# NT1X68BC.net
KiCad netlist of a schematic drawn in EAGLE
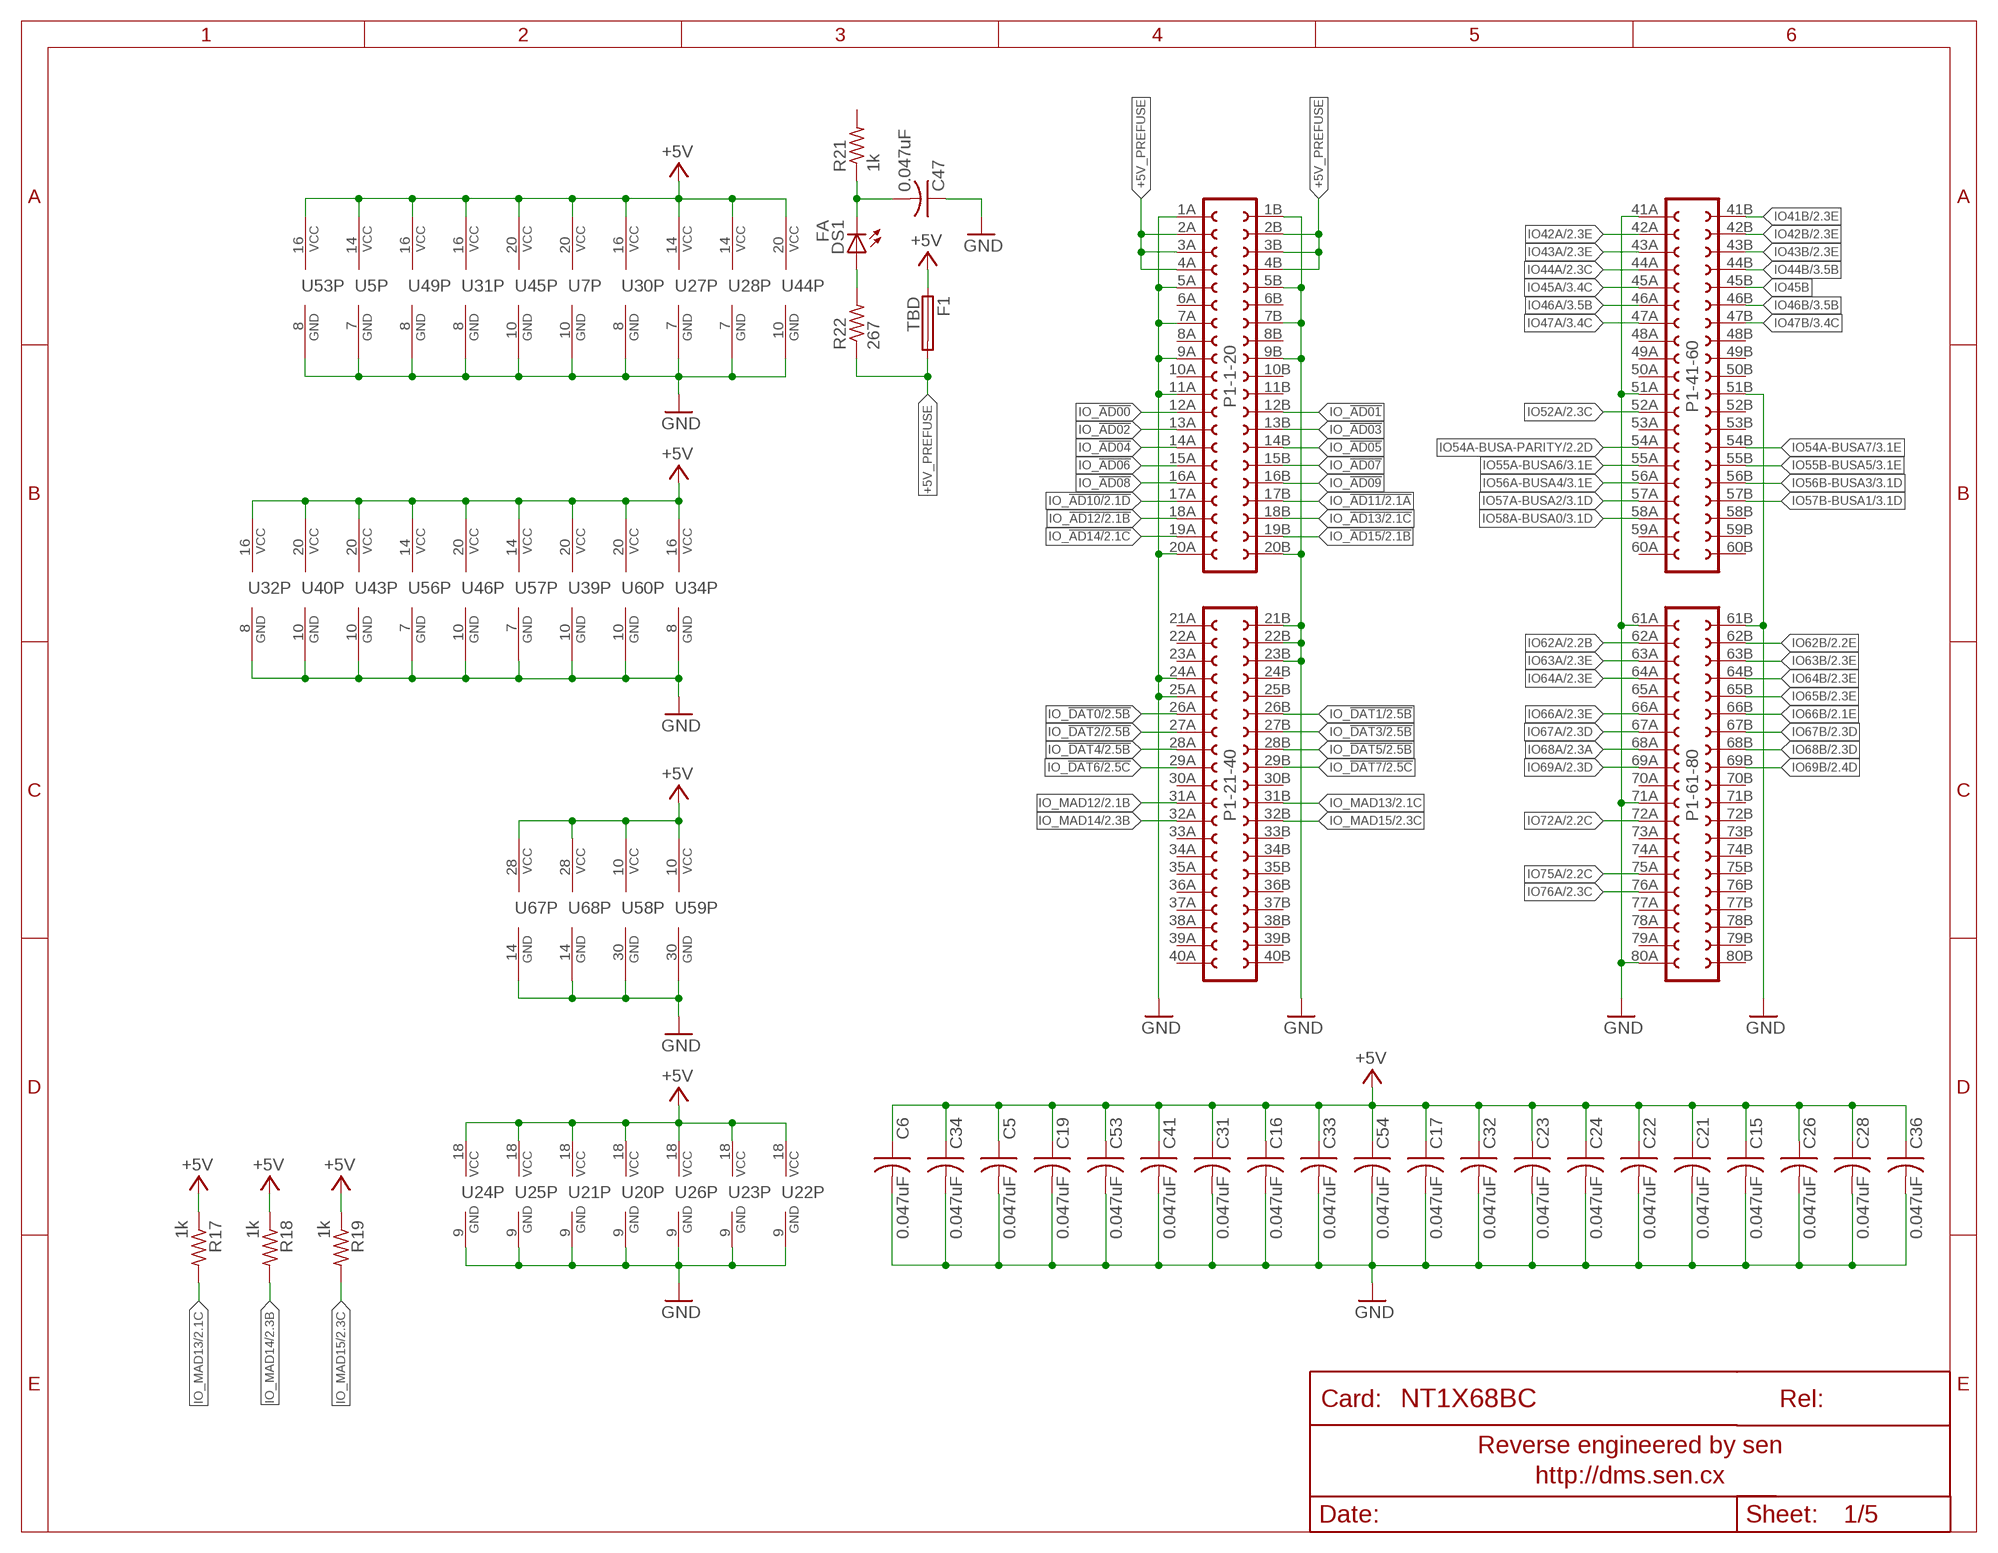
[diagram p0: schematic, sheet 1]
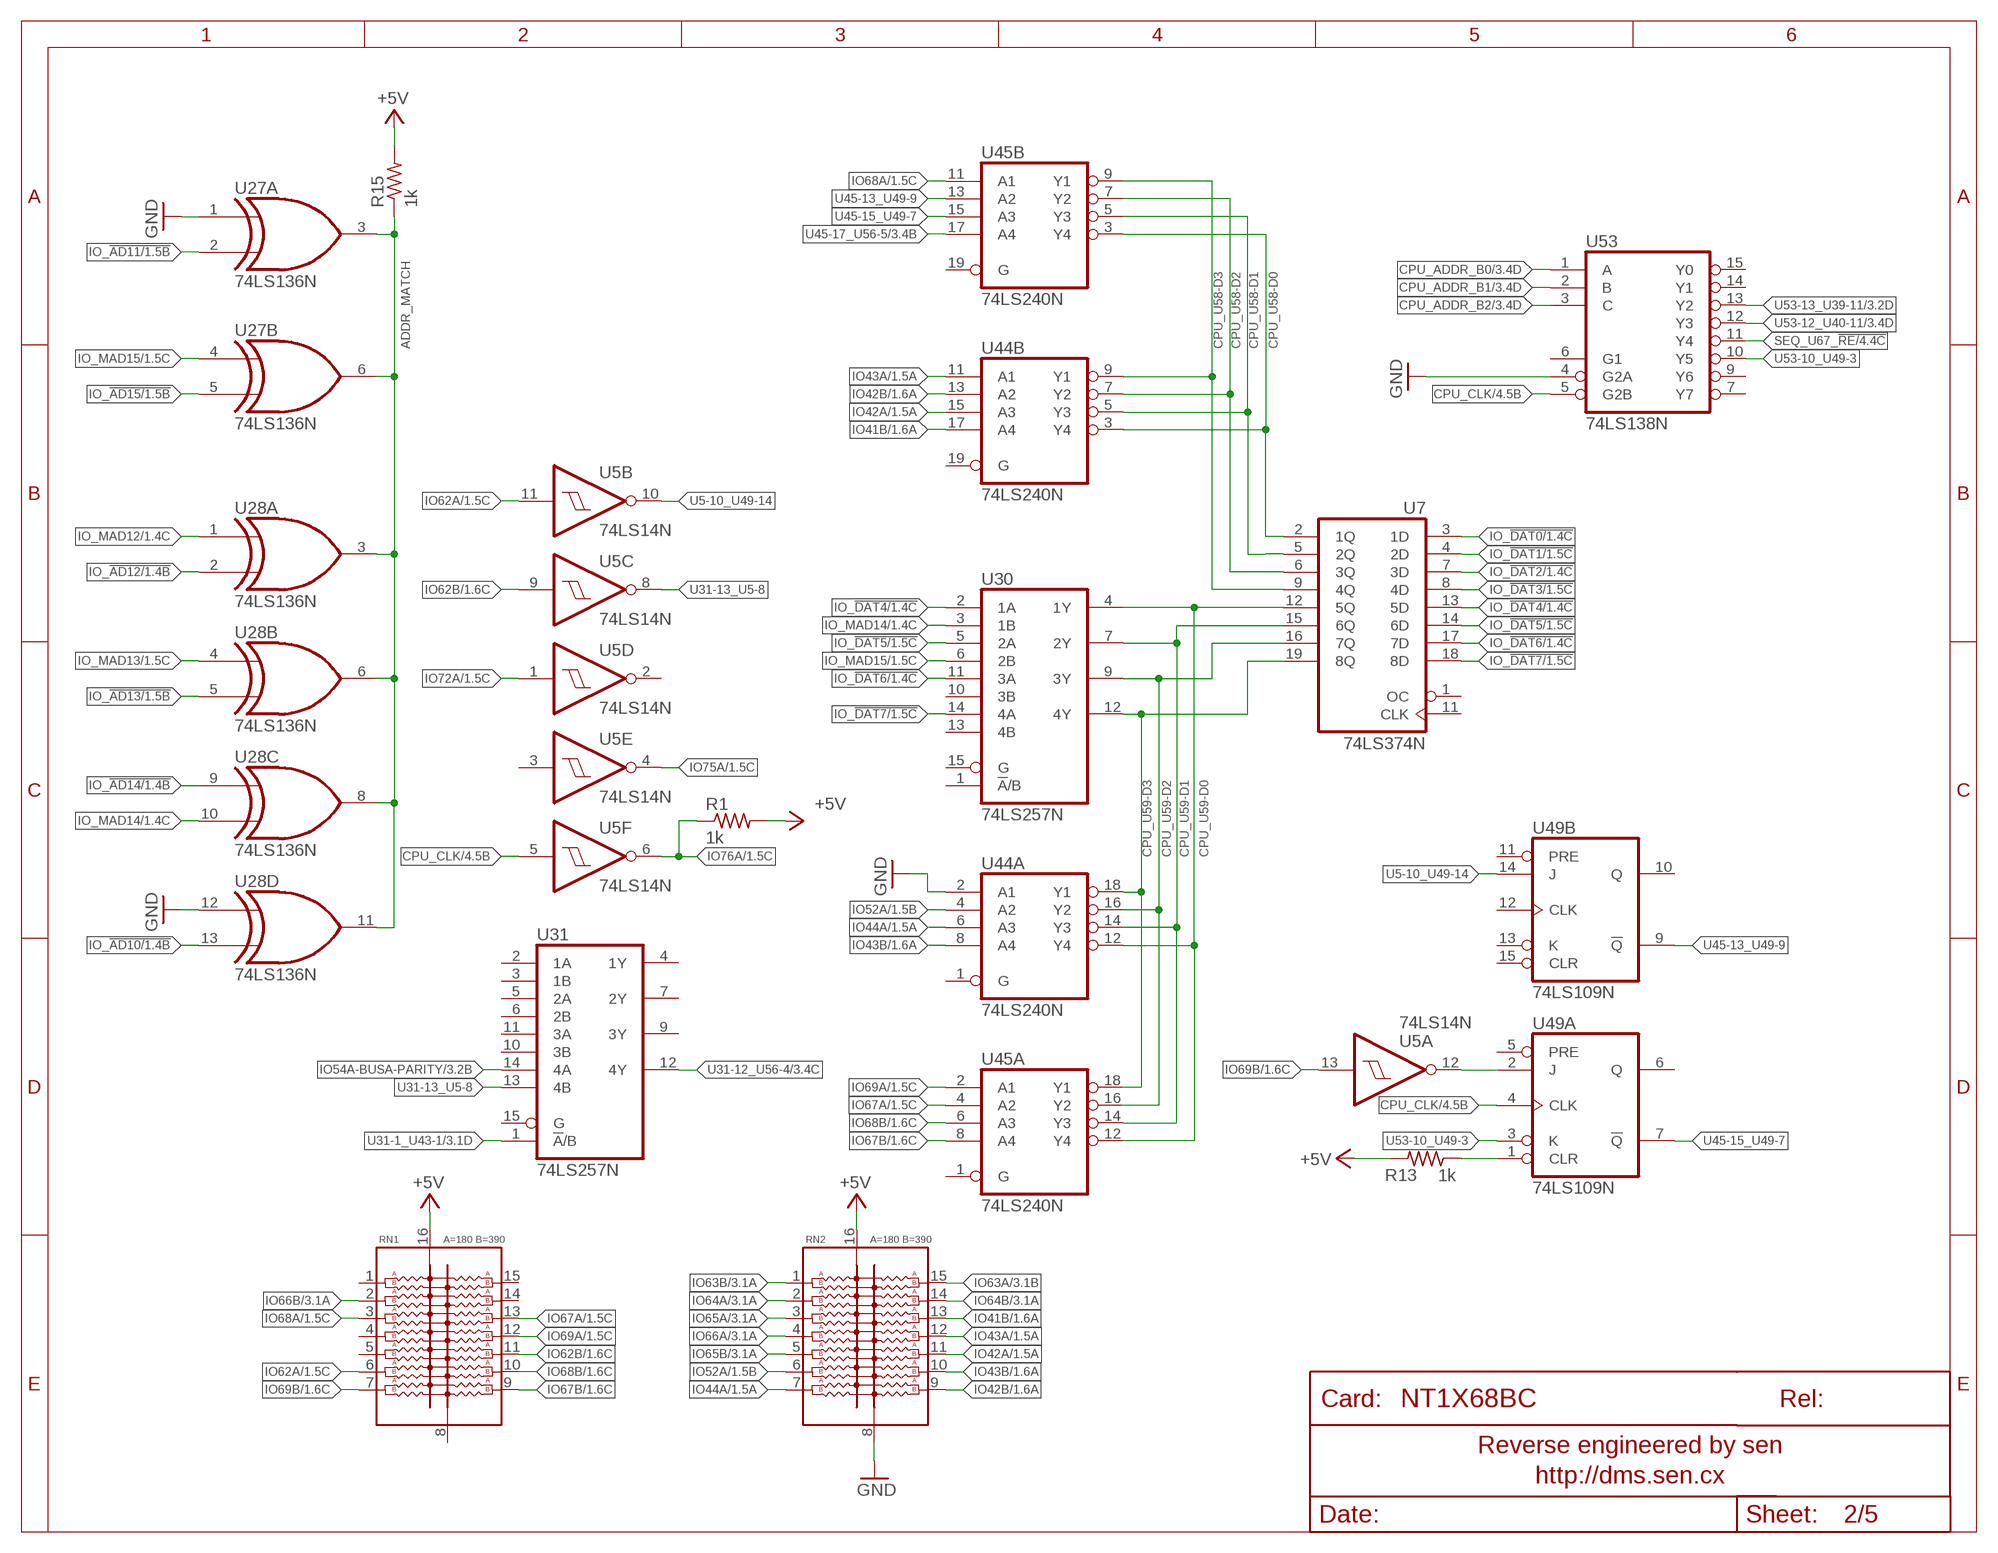
[diagram p1: schematic, sheet 2]
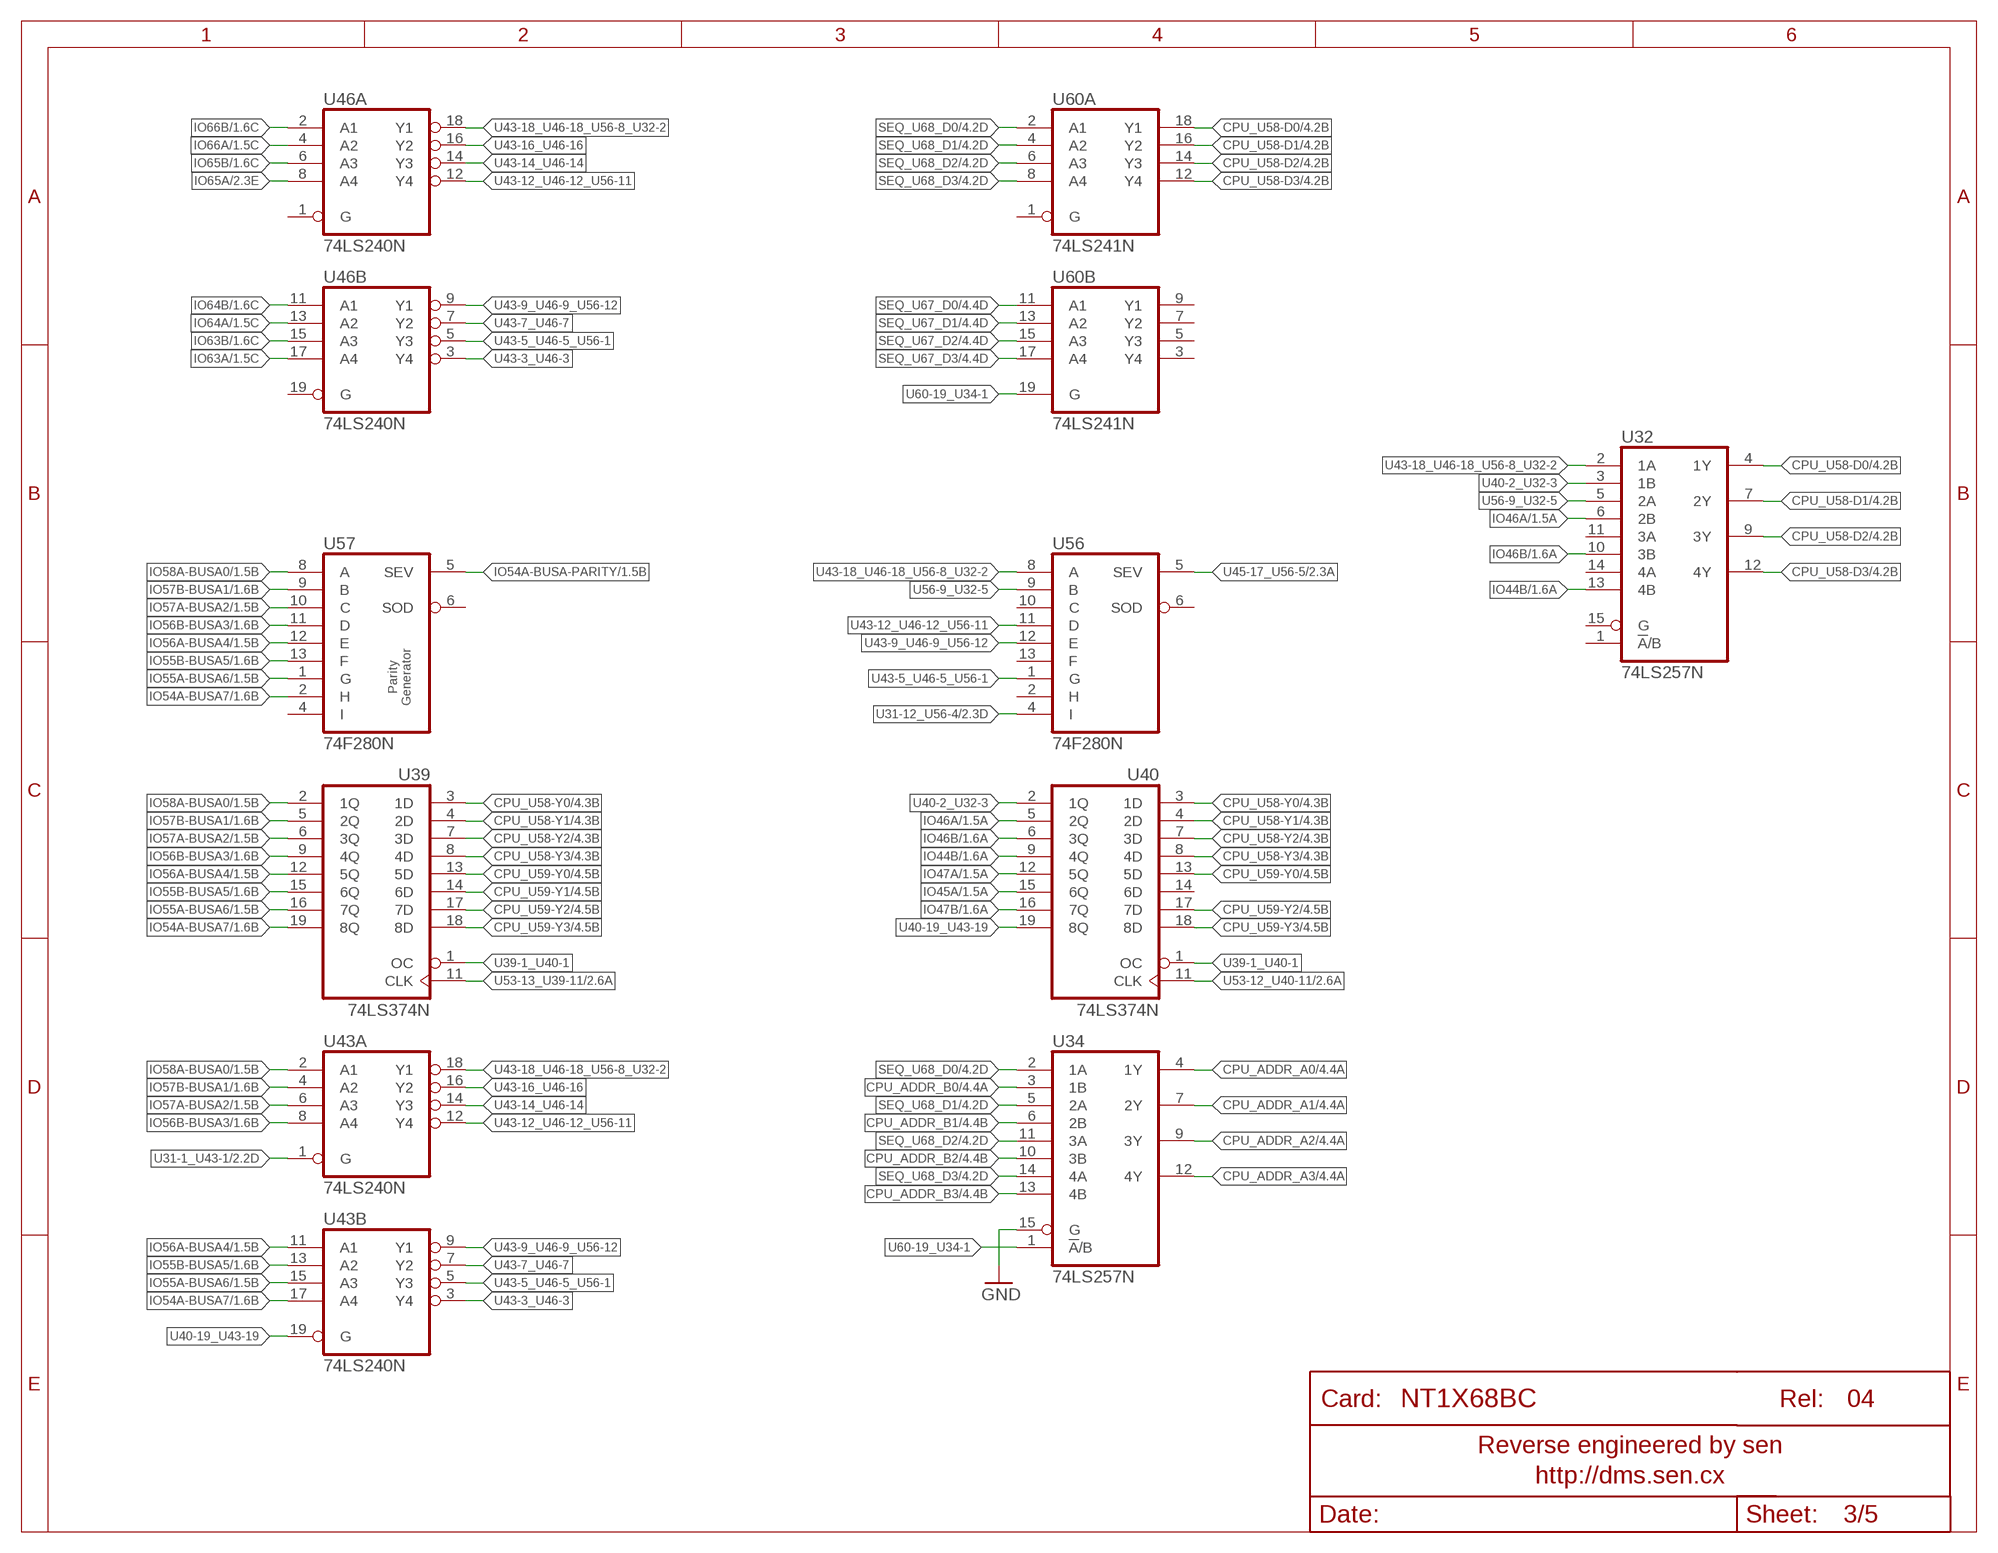
[diagram p2: schematic, sheet 3]
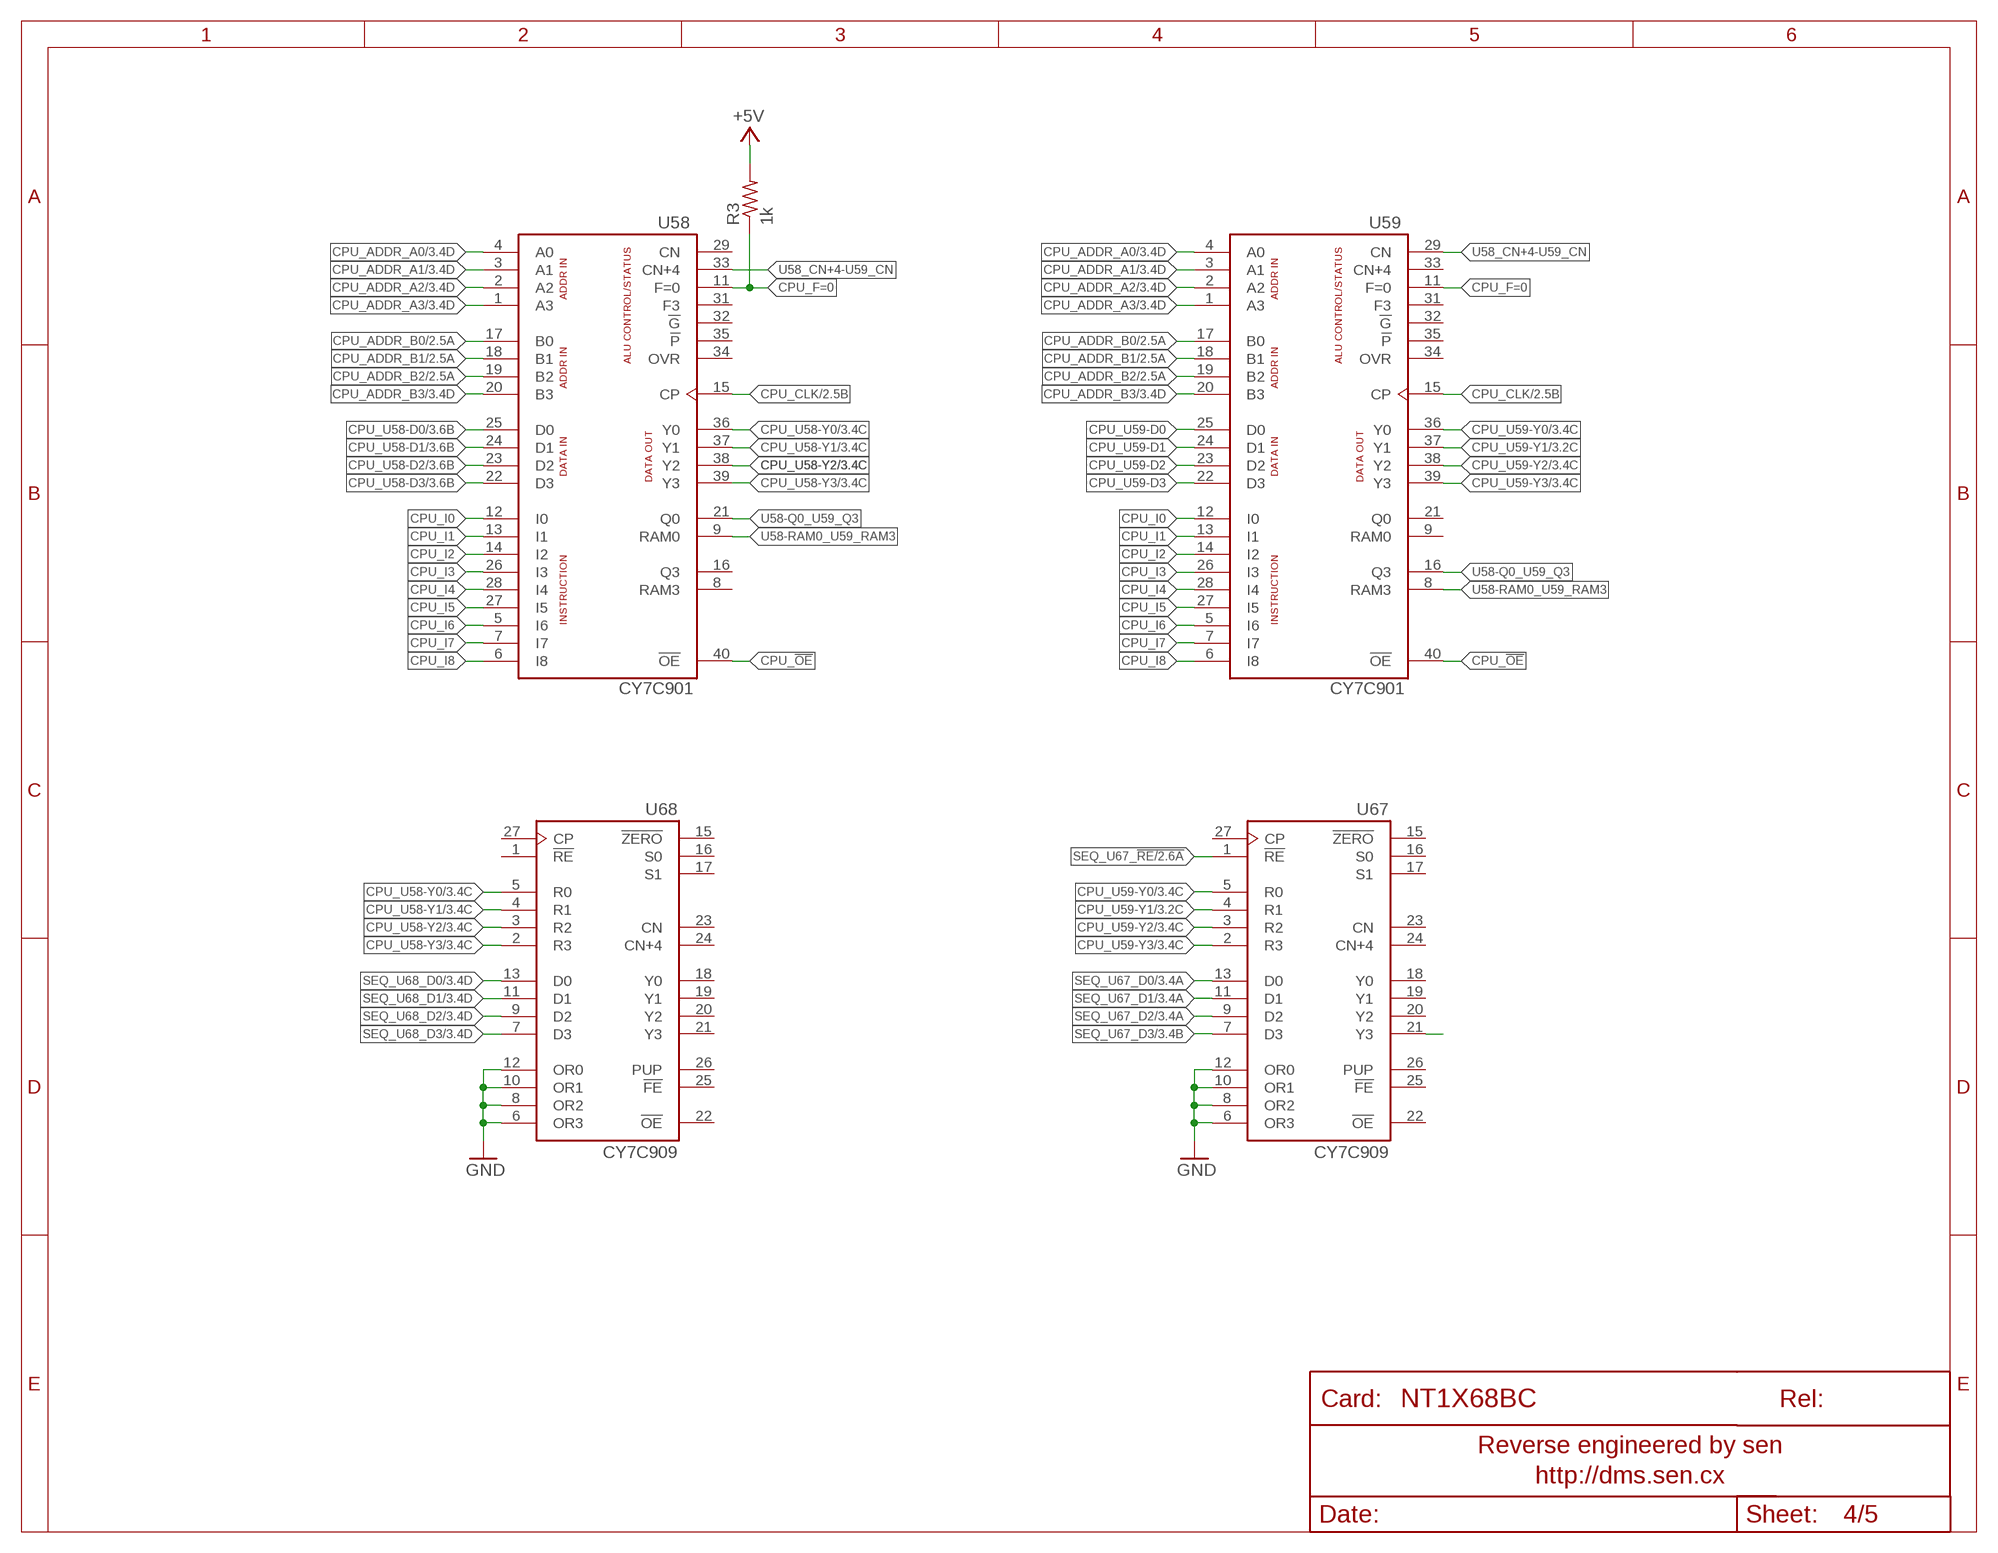
[diagram p3: schematic, sheet 4]
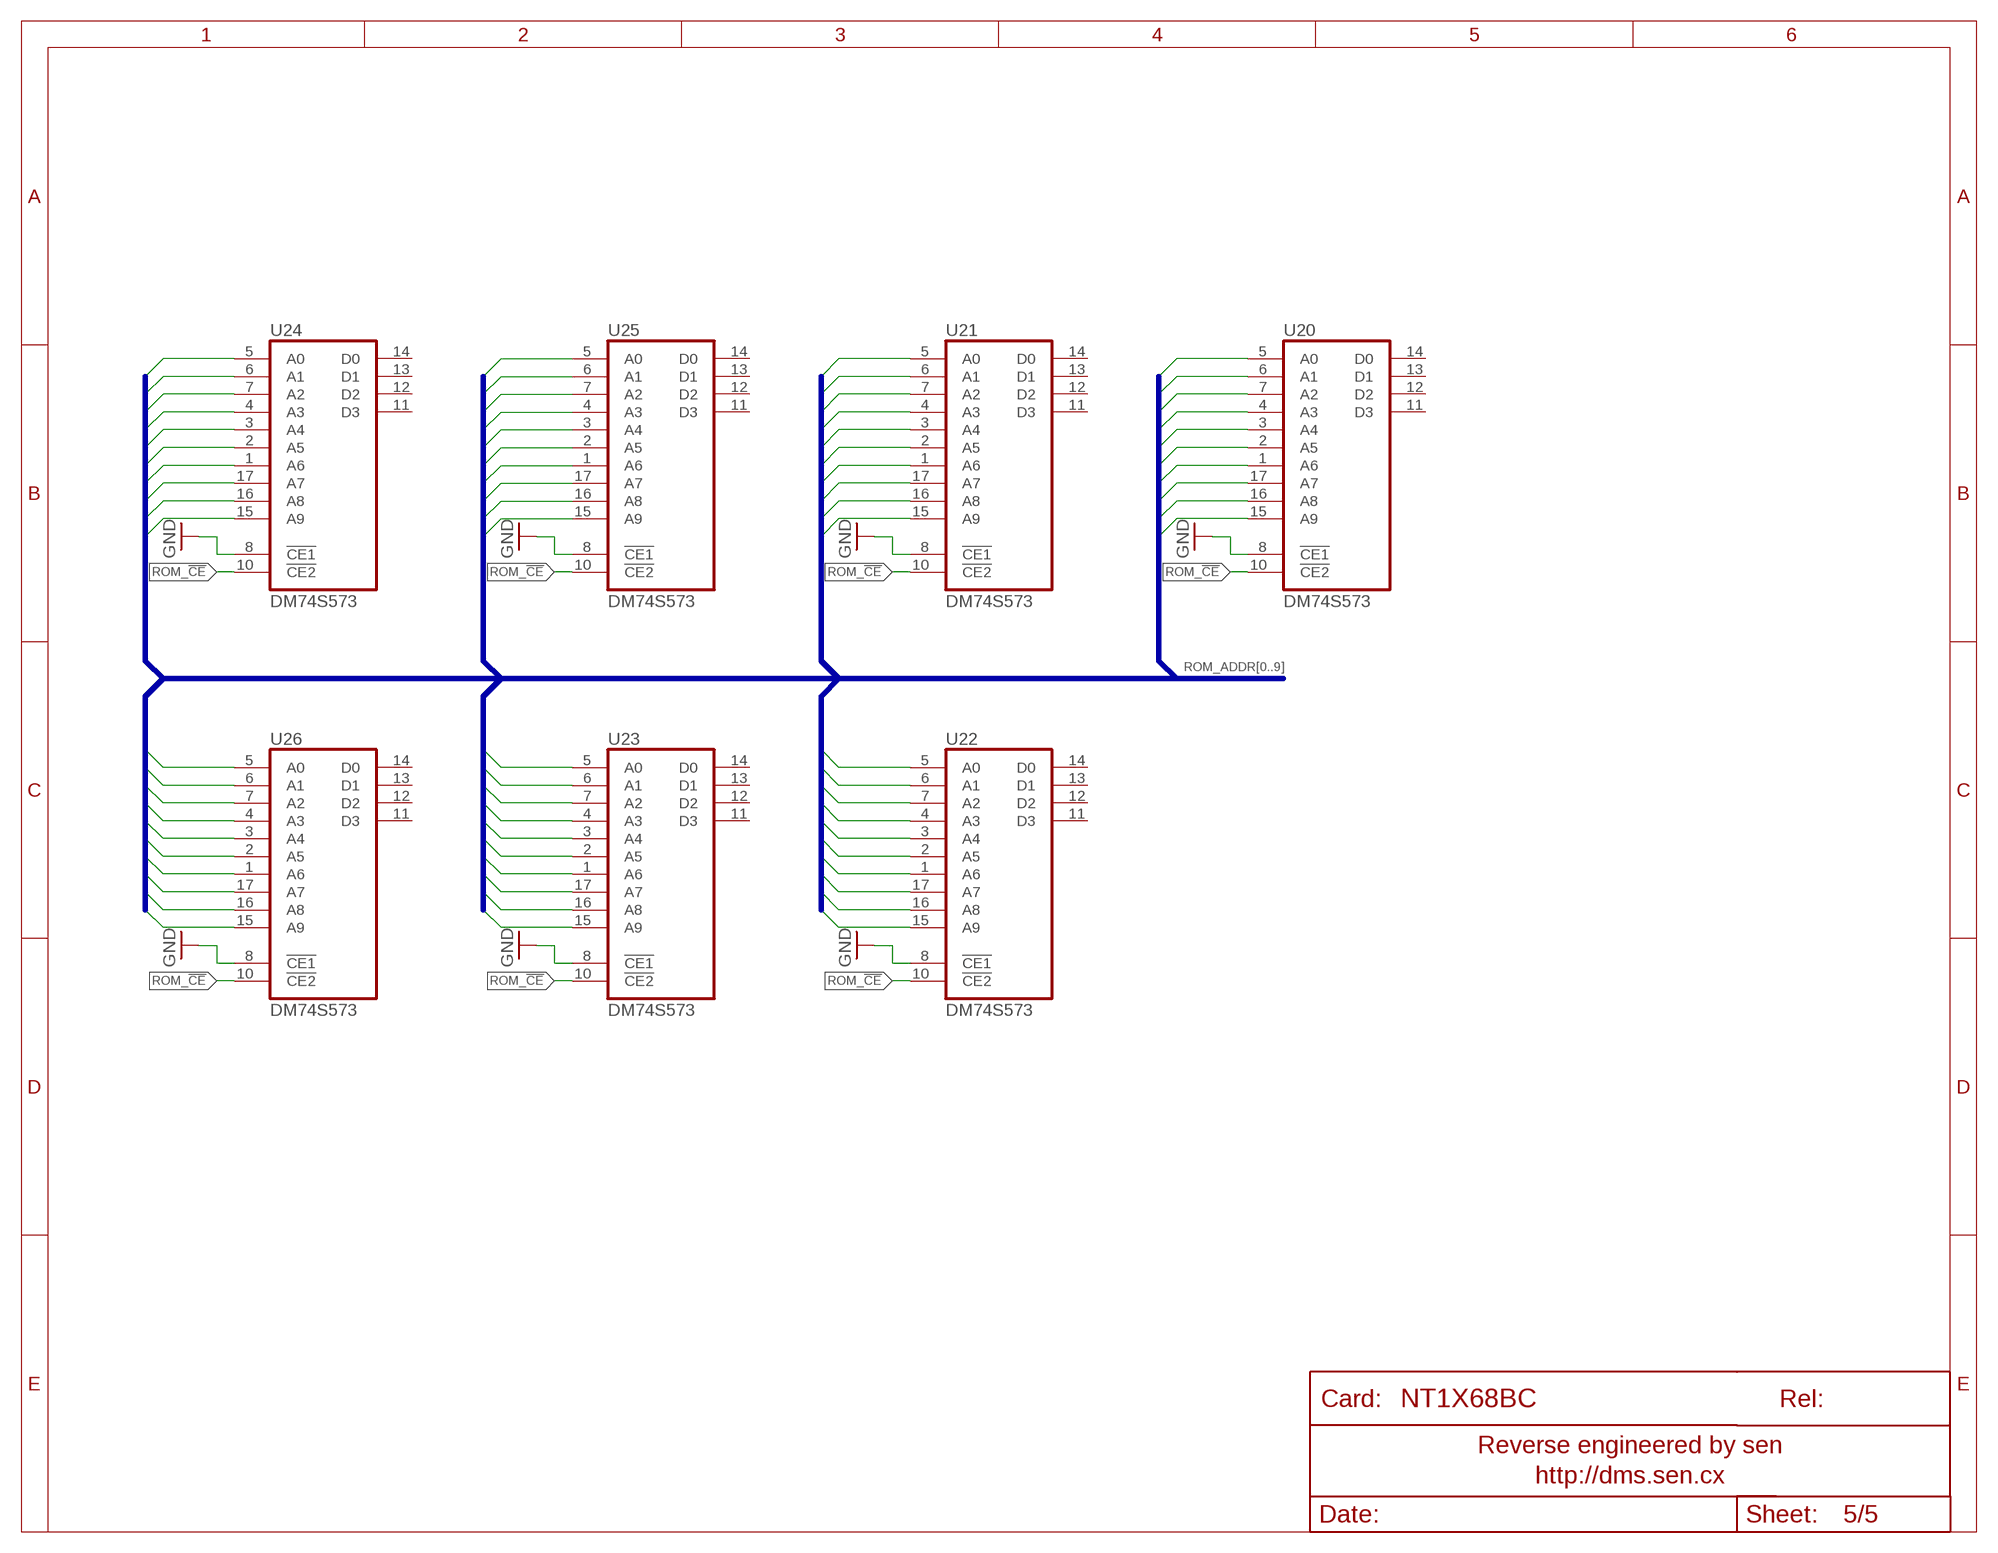
[diagram p4: schematic, sheet 5]

(export (version "E")
  (design (tool "Eeschema 10.0.6"))
  (components
    (comp (ref "R1")
      (value "1k")
      (footprint "eagle-import:0207_12")
      (libsource (lib "eagle-import") (part "R-US_0207/12"))
    )
    (comp (ref "R13")
      (value "1k")
      (footprint "eagle-import:0207_12")
      (libsource (lib "eagle-import") (part "R-US_0207/12"))
    )
    (comp (ref "R15")
      (value "1k")
      (footprint "eagle-import:0207_12")
      (libsource (lib "eagle-import") (part "R-US_0207/12"))
    )
    (comp (ref "RN1")
      (value "A=180 B=390")
      (footprint "eagle-import:DIL16")
      (libsource (lib "eagle-import") (part "DALE-MDP1605"))
    )
    (comp (ref "RN2")
      (value "A=180 B=390")
      (footprint "eagle-import:DIL16")
      (libsource (lib "eagle-import") (part "DALE-MDP1605"))
    )
    (comp (ref "U5")
      (value "74LS14N")
      (footprint "eagle-import:DIL14")
      (libsource (lib "eagle-import") (part "7414NLS"))
    )
    (comp (ref "U7")
      (value "74LS374N")
      (footprint "eagle-import:DIL20")
      (libsource (lib "eagle-import") (part "74374NLS"))
    )
    (comp (ref "U27")
      (value "74LS136N")
      (footprint "eagle-import:DIL14")
      (libsource (lib "eagle-import") (part "74136NLS"))
    )
    (comp (ref "U28")
      (value "74LS136N")
      (footprint "eagle-import:DIL14")
      (libsource (lib "eagle-import") (part "74136NLS"))
    )
    (comp (ref "U30")
      (value "74LS257N")
      (footprint "eagle-import:DIL16")
      (libsource (lib "eagle-import") (part "74257NLS"))
    )
    (comp (ref "U31")
      (value "74LS257N")
      (footprint "eagle-import:DIL16")
      (libsource (lib "eagle-import") (part "74257NLS"))
    )
    (comp (ref "U44")
      (value "74LS240N")
      (footprint "eagle-import:DIL20")
      (libsource (lib "eagle-import") (part "74240NLS"))
    )
    (comp (ref "U45")
      (value "74LS240N")
      (footprint "eagle-import:DIL20")
      (libsource (lib "eagle-import") (part "74240NLS"))
    )
    (comp (ref "U49")
      (value "74LS109N")
      (footprint "eagle-import:DIL16")
      (libsource (lib "eagle-import") (part "74109NLS"))
    )
    (comp (ref "U53")
      (value "74LS138N")
      (footprint "eagle-import:DIL16")
      (libsource (lib "eagle-import") (part "74138NLS"))
    )
    (comp (ref "C5")
      (value "0.047uF")
      (footprint "eagle-import:C075-032X103")
      (libsource (lib "eagle-import") (part "C-US075-032X103"))
    )
    (comp (ref "C6")
      (value "0.047uF")
      (footprint "eagle-import:C075-032X103")
      (libsource (lib "eagle-import") (part "C-US075-032X103"))
    )
    (comp (ref "C15")
      (value "0.047uF")
      (footprint "eagle-import:C075-032X103")
      (libsource (lib "eagle-import") (part "C-US075-032X103"))
    )
    (comp (ref "C16")
      (value "0.047uF")
      (footprint "eagle-import:C075-032X103")
      (libsource (lib "eagle-import") (part "C-US075-032X103"))
    )
    (comp (ref "C17")
      (value "0.047uF")
      (footprint "eagle-import:C075-032X103")
      (libsource (lib "eagle-import") (part "C-US075-032X103"))
    )
    (comp (ref "C19")
      (value "0.047uF")
      (footprint "eagle-import:C075-032X103")
      (libsource (lib "eagle-import") (part "C-US075-032X103"))
    )
    (comp (ref "C21")
      (value "0.047uF")
      (footprint "eagle-import:C075-032X103")
      (libsource (lib "eagle-import") (part "C-US075-032X103"))
    )
    (comp (ref "C22")
      (value "0.047uF")
      (footprint "eagle-import:C075-032X103")
      (libsource (lib "eagle-import") (part "C-US075-032X103"))
    )
    (comp (ref "C23")
      (value "0.047uF")
      (footprint "eagle-import:C075-032X103")
      (libsource (lib "eagle-import") (part "C-US075-032X103"))
    )
    (comp (ref "C24")
      (value "0.047uF")
      (footprint "eagle-import:C075-032X103")
      (libsource (lib "eagle-import") (part "C-US075-032X103"))
    )
    (comp (ref "C26")
      (value "0.047uF")
      (footprint "eagle-import:C075-032X103")
      (libsource (lib "eagle-import") (part "C-US075-032X103"))
    )
    (comp (ref "C28")
      (value "0.047uF")
      (footprint "eagle-import:C075-032X103")
      (libsource (lib "eagle-import") (part "C-US075-032X103"))
    )
    (comp (ref "C31")
      (value "0.047uF")
      (footprint "eagle-import:C075-032X103")
      (libsource (lib "eagle-import") (part "C-US075-032X103"))
    )
    (comp (ref "C32")
      (value "0.047uF")
      (footprint "eagle-import:C075-032X103")
      (libsource (lib "eagle-import") (part "C-US075-032X103"))
    )
    (comp (ref "C33")
      (value "0.047uF")
      (footprint "eagle-import:C075-032X103")
      (libsource (lib "eagle-import") (part "C-US075-032X103"))
    )
    (comp (ref "C34")
      (value "0.047uF")
      (footprint "eagle-import:C075-032X103")
      (libsource (lib "eagle-import") (part "C-US075-032X103"))
    )
    (comp (ref "C36")
      (value "0.047uF")
      (footprint "eagle-import:C075-032X103")
      (libsource (lib "eagle-import") (part "C-US075-032X103"))
    )
    (comp (ref "C41")
      (value "0.047uF")
      (footprint "eagle-import:C075-032X103")
      (libsource (lib "eagle-import") (part "C-US075-032X103"))
    )
    (comp (ref "C47")
      (value "0.047uF")
      (footprint "eagle-import:C075-032X103")
      (libsource (lib "eagle-import") (part "C-US075-032X103"))
    )
    (comp (ref "C53")
      (value "0.047uF")
      (footprint "eagle-import:C075-032X103")
      (libsource (lib "eagle-import") (part "C-US075-032X103"))
    )
    (comp (ref "C54")
      (value "0.047uF")
      (footprint "eagle-import:C075-032X103")
      (libsource (lib "eagle-import") (part "C-US075-032X103"))
    )
    (comp (ref "DS1")
      (value "FA")
      (footprint "eagle-import:LED5MM")
      (libsource (lib "eagle-import") (part "LED5MM"))
    )
    (comp (ref "F1")
      (value "TBD")
      (footprint "eagle-import:LITTLEFUSE")
      (libsource (lib "eagle-import") (part "LITTLEFUSE"))
    )
    (comp (ref "P1")
      (value "FE80-2W-HALFKEY")
      (footprint "eagle-import:FE80-2W-HALFKEY")
      (libsource (lib "eagle-import") (part "FE80-2W-HALFKEY"))
    )
    (comp (ref "R17")
      (value "1k")
      (footprint "eagle-import:0207_12")
      (libsource (lib "eagle-import") (part "R-US_0207/12"))
    )
    (comp (ref "R18")
      (value "1k")
      (footprint "eagle-import:0207_12")
      (libsource (lib "eagle-import") (part "R-US_0207/12"))
    )
    (comp (ref "R19")
      (value "1k")
      (footprint "eagle-import:0207_12")
      (libsource (lib "eagle-import") (part "R-US_0207/12"))
    )
    (comp (ref "R21")
      (value "1k")
      (footprint "eagle-import:0207_12")
      (libsource (lib "eagle-import") (part "R-US_0207/12"))
    )
    (comp (ref "R22")
      (value "267")
      (footprint "eagle-import:0207_12")
      (libsource (lib "eagle-import") (part "R-US_0207/12"))
    )
    (comp (ref "U20")
      (value "DM74S573")
      (footprint "eagle-import:DIL18")
      (libsource (lib "eagle-import") (part "DM74S573"))
    )
    (comp (ref "U21")
      (value "DM74S573")
      (footprint "eagle-import:DIL18")
      (libsource (lib "eagle-import") (part "DM74S573"))
    )
    (comp (ref "U22")
      (value "DM74S573")
      (footprint "eagle-import:DIL18")
      (libsource (lib "eagle-import") (part "DM74S573"))
    )
    (comp (ref "U23")
      (value "DM74S573")
      (footprint "eagle-import:DIL18")
      (libsource (lib "eagle-import") (part "DM74S573"))
    )
    (comp (ref "U24")
      (value "DM74S573")
      (footprint "eagle-import:DIL18")
      (libsource (lib "eagle-import") (part "DM74S573"))
    )
    (comp (ref "U25")
      (value "DM74S573")
      (footprint "eagle-import:DIL18")
      (libsource (lib "eagle-import") (part "DM74S573"))
    )
    (comp (ref "U26")
      (value "DM74S573")
      (footprint "eagle-import:DIL18")
      (libsource (lib "eagle-import") (part "DM74S573"))
    )
    (comp (ref "U32")
      (value "74LS257N")
      (footprint "eagle-import:DIL16")
      (libsource (lib "eagle-import") (part "74257NLS"))
    )
    (comp (ref "U34")
      (value "74LS257N")
      (footprint "eagle-import:DIL16")
      (libsource (lib "eagle-import") (part "74257NLS"))
    )
    (comp (ref "U39")
      (value "74LS374N")
      (footprint "eagle-import:DIL20")
      (libsource (lib "eagle-import") (part "74374NLS"))
    )
    (comp (ref "U40")
      (value "74LS374N")
      (footprint "eagle-import:DIL20")
      (libsource (lib "eagle-import") (part "74374NLS"))
    )
    (comp (ref "U43")
      (value "74LS240N")
      (footprint "eagle-import:DIL20")
      (libsource (lib "eagle-import") (part "74240NLS"))
    )
    (comp (ref "U46")
      (value "74LS240N")
      (footprint "eagle-import:DIL20")
      (libsource (lib "eagle-import") (part "74240NLS"))
    )
    (comp (ref "U56")
      (value "74F280N")
      (footprint "eagle-import:DIL14")
      (libsource (lib "eagle-import") (part "74280NLS"))
    )
    (comp (ref "U57")
      (value "74F280N")
      (footprint "eagle-import:DIL14")
      (libsource (lib "eagle-import") (part "74280NLS"))
    )
    (comp (ref "U58")
      (value "CY7C901")
      (footprint "eagle-import:DIL40")
      (libsource (lib "eagle-import") (part "CY7C901"))
    )
    (comp (ref "U59")
      (value "CY7C901")
      (footprint "eagle-import:DIL40")
      (libsource (lib "eagle-import") (part "CY7C901"))
    )
    (comp (ref "U60")
      (value "74LS241N")
      (footprint "eagle-import:DIL20")
      (libsource (lib "eagle-import") (part "74241NLS"))
    )
    (comp (ref "U67")
      (value "CY7C909")
      (footprint "eagle-import:DIL28-6")
      (libsource (lib "eagle-import") (part "CY7C909"))
    )
    (comp (ref "U68")
      (value "CY7C909")
      (footprint "eagle-import:DIL28-6")
      (libsource (lib "eagle-import") (part "CY7C909"))
    )
    (comp (ref "R3")
      (value "1k")
      (footprint "eagle-import:0207_12")
      (libsource (lib "eagle-import") (part "R-US_0207/12"))
    )
  )
  (nets
    (net (code "1") (name "+5V") (class "Default")
      (node (ref "C15") (pin "1") (pinfunction "1_1") (pintype "passive"))
      (node (ref "C16") (pin "1") (pinfunction "1_1") (pintype "passive"))
      (node (ref "C17") (pin "1") (pinfunction "1_1") (pintype "passive"))
      (node (ref "C19") (pin "1") (pinfunction "1_1") (pintype "passive"))
      (node (ref "C21") (pin "1") (pinfunction "1_1") (pintype "passive"))
      (node (ref "C22") (pin "1") (pinfunction "1_1") (pintype "passive"))
      (node (ref "C23") (pin "1") (pinfunction "1_1") (pintype "passive"))
      (node (ref "C24") (pin "1") (pinfunction "1_1") (pintype "passive"))
      (node (ref "C26") (pin "1") (pinfunction "1_1") (pintype "passive"))
      (node (ref "C28") (pin "1") (pinfunction "1_1") (pintype "passive"))
      (node (ref "C31") (pin "1") (pinfunction "1_1") (pintype "passive"))
      (node (ref "C32") (pin "1") (pinfunction "1_1") (pintype "passive"))
      (node (ref "C33") (pin "1") (pinfunction "1_1") (pintype "passive"))
      (node (ref "C34") (pin "1") (pinfunction "1_1") (pintype "passive"))
      (node (ref "C36") (pin "1") (pinfunction "1_1") (pintype "passive"))
      (node (ref "C41") (pin "1") (pinfunction "1_1") (pintype "passive"))
      (node (ref "C5") (pin "1") (pinfunction "1_1") (pintype "passive"))
      (node (ref "C53") (pin "1") (pinfunction "1_1") (pintype "passive"))
      (node (ref "C54") (pin "1") (pinfunction "1_1") (pintype "passive"))
      (node (ref "C6") (pin "1") (pinfunction "1_1") (pintype "passive"))
      (node (ref "F1") (pin "1") (pinfunction "1_1") (pintype "passive"))
      (node (ref "R1") (pin "2") (pinfunction "2_2") (pintype "passive"))
      (node (ref "R13") (pin "2") (pinfunction "2_2") (pintype "passive"))
      (node (ref "R15") (pin "2") (pinfunction "2_2") (pintype "passive"))
      (node (ref "R17") (pin "1") (pinfunction "1_1") (pintype "passive"))
      (node (ref "R18") (pin "1") (pinfunction "1_1") (pintype "passive"))
      (node (ref "R19") (pin "1") (pinfunction "1_1") (pintype "passive"))
      (node (ref "R3") (pin "2") (pinfunction "2_2") (pintype "passive"))
      (node (ref "RN1") (pin "16") (pinfunction "A_16") (pintype "passive"))
      (node (ref "RN2") (pin "16") (pinfunction "A_16") (pintype "passive"))
      (node (ref "U20") (pin "18") (pinfunction "VCC_18") (pintype "power_in"))
      (node (ref "U21") (pin "18") (pinfunction "VCC_18") (pintype "power_in"))
      (node (ref "U22") (pin "18") (pinfunction "VCC_18") (pintype "power_in"))
      (node (ref "U23") (pin "18") (pinfunction "VCC_18") (pintype "power_in"))
      (node (ref "U24") (pin "18") (pinfunction "VCC_18") (pintype "power_in"))
      (node (ref "U25") (pin "18") (pinfunction "VCC_18") (pintype "power_in"))
      (node (ref "U26") (pin "18") (pinfunction "VCC_18") (pintype "power_in"))
      (node (ref "U27") (pin "14") (pinfunction "VCC_14") (pintype "power_in"))
      (node (ref "U28") (pin "14") (pinfunction "VCC_14") (pintype "power_in"))
      (node (ref "U30") (pin "16") (pinfunction "VCC_16") (pintype "power_in"))
      (node (ref "U31") (pin "16") (pinfunction "VCC_16") (pintype "power_in"))
      (node (ref "U32") (pin "16") (pinfunction "VCC_16") (pintype "power_in"))
      (node (ref "U34") (pin "16") (pinfunction "VCC_16") (pintype "power_in"))
      (node (ref "U39") (pin "20") (pinfunction "VCC_20") (pintype "power_in"))
      (node (ref "U40") (pin "20") (pinfunction "VCC_20") (pintype "power_in"))
      (node (ref "U43") (pin "20") (pinfunction "VCC_20") (pintype "power_in"))
      (node (ref "U44") (pin "20") (pinfunction "VCC_20") (pintype "power_in"))
      (node (ref "U45") (pin "20") (pinfunction "VCC_20") (pintype "power_in"))
      (node (ref "U46") (pin "20") (pinfunction "VCC_20") (pintype "power_in"))
      (node (ref "U49") (pin "16") (pinfunction "VCC_16") (pintype "power_in"))
      (node (ref "U5") (pin "14") (pinfunction "VCC_14") (pintype "power_in"))
      (node (ref "U53") (pin "16") (pinfunction "VCC_16") (pintype "power_in"))
      (node (ref "U56") (pin "14") (pinfunction "VCC_14") (pintype "power_in"))
      (node (ref "U57") (pin "14") (pinfunction "VCC_14") (pintype "power_in"))
      (node (ref "U58") (pin "10") (pinfunction "VCC_10") (pintype "power_in"))
      (node (ref "U59") (pin "10") (pinfunction "VCC_10") (pintype "power_in"))
      (node (ref "U60") (pin "20") (pinfunction "VCC_20") (pintype "power_in"))
      (node (ref "U67") (pin "28") (pinfunction "VCC_28") (pintype "power_in"))
      (node (ref "U68") (pin "28") (pinfunction "VCC_28") (pintype "power_in"))
      (node (ref "U7") (pin "20") (pinfunction "VCC_20") (pintype "power_in"))
    )
    (net (code "2") (name "+5V_PREFUSE") (class "Default")
      (node (ref "F1") (pin "2") (pinfunction "2_2") (pintype "passive"))
      (node (ref "P1") (pin "2A") (pinfunction "2A_2A") (pintype "passive"))
      (node (ref "P1") (pin "2B") (pinfunction "2B_2B") (pintype "passive"))
      (node (ref "P1") (pin "3A") (pinfunction "3A_3A") (pintype "passive"))
      (node (ref "P1") (pin "3B") (pinfunction "3B_3B") (pintype "passive"))
      (node (ref "P1") (pin "4A") (pinfunction "4A_4A") (pintype "passive"))
      (node (ref "P1") (pin "4B") (pinfunction "4B_4B") (pintype "passive"))
      (node (ref "R22") (pin "1") (pinfunction "1_1") (pintype "passive"))
    )
    (net (code "4") (name "ADDR_MATCH") (class "Default")
      (node (ref "R15") (pin "1") (pinfunction "1_1") (pintype "passive"))
      (node (ref "U27") (pin "3") (pinfunction "O_3") (pintype "open_collector"))
      (node (ref "U27") (pin "6") (pinfunction "O_6") (pintype "open_collector"))
      (node (ref "U28") (pin "11") (pinfunction "O_11") (pintype "open_collector"))
      (node (ref "U28") (pin "3") (pinfunction "O_3") (pintype "open_collector"))
      (node (ref "U28") (pin "6") (pinfunction "O_6") (pintype "open_collector"))
      (node (ref "U28") (pin "8") (pinfunction "O_8") (pintype "open_collector"))
    )
    (net (code "5") (name "CPU_ADDR_A0") (class "Default")
      (node (ref "U34") (pin "4") (pinfunction "1Y_4") (pintype "tri_state"))
      (node (ref "U58") (pin "4") (pinfunction "A0_4") (pintype "input"))
      (node (ref "U59") (pin "4") (pinfunction "A0_4") (pintype "input"))
    )
    (net (code "6") (name "CPU_ADDR_A1") (class "Default")
      (node (ref "U34") (pin "7") (pinfunction "2Y_7") (pintype "tri_state"))
      (node (ref "U58") (pin "3") (pinfunction "A1_3") (pintype "input"))
      (node (ref "U59") (pin "3") (pinfunction "A1_3") (pintype "input"))
    )
    (net (code "7") (name "CPU_ADDR_A2") (class "Default")
      (node (ref "U34") (pin "9") (pinfunction "3Y_9") (pintype "tri_state"))
      (node (ref "U58") (pin "2") (pinfunction "A2_2") (pintype "input"))
      (node (ref "U59") (pin "2") (pinfunction "A2_2") (pintype "input"))
    )
    (net (code "8") (name "CPU_ADDR_A3") (class "Default")
      (node (ref "U34") (pin "12") (pinfunction "4Y_12") (pintype "tri_state"))
      (node (ref "U58") (pin "1") (pinfunction "A3_1") (pintype "input"))
      (node (ref "U59") (pin "1") (pinfunction "A3_1") (pintype "input"))
    )
    (net (code "9") (name "CPU_ADDR_B0") (class "Default")
      (node (ref "U34") (pin "3") (pinfunction "1B_3") (pintype "input"))
      (node (ref "U53") (pin "1") (pinfunction "A_1") (pintype "input"))
      (node (ref "U58") (pin "17") (pinfunction "B0_17") (pintype "input"))
      (node (ref "U59") (pin "17") (pinfunction "B0_17") (pintype "input"))
    )
    (net (code "10") (name "CPU_ADDR_B1") (class "Default")
      (node (ref "U34") (pin "6") (pinfunction "2B_6") (pintype "input"))
      (node (ref "U53") (pin "2") (pinfunction "B_2") (pintype "input"))
      (node (ref "U58") (pin "18") (pinfunction "B1_18") (pintype "input"))
      (node (ref "U59") (pin "18") (pinfunction "B1_18") (pintype "input"))
    )
    (net (code "11") (name "CPU_ADDR_B2") (class "Default")
      (node (ref "U34") (pin "10") (pinfunction "3B_10") (pintype "input"))
      (node (ref "U53") (pin "3") (pinfunction "C_3") (pintype "input"))
      (node (ref "U58") (pin "19") (pinfunction "B2_19") (pintype "input"))
      (node (ref "U59") (pin "19") (pinfunction "B2_19") (pintype "input"))
    )
    (net (code "12") (name "CPU_ADDR_B3") (class "Default")
      (node (ref "U34") (pin "13") (pinfunction "4B_13") (pintype "input"))
      (node (ref "U58") (pin "20") (pinfunction "B3_20") (pintype "input"))
      (node (ref "U59") (pin "20") (pinfunction "B3_20") (pintype "input"))
    )
    (net (code "13") (name "CPU_CLK") (class "Default")
      (node (ref "U49") (pin "4") (pinfunction "CLK_4") (pintype "input"))
      (node (ref "U5") (pin "5") (pinfunction "I_5") (pintype "input"))
      (node (ref "U53") (pin "5") (pinfunction "G2B_5") (pintype "input"))
      (node (ref "U58") (pin "15") (pinfunction "CP_15") (pintype "input"))
      (node (ref "U59") (pin "15") (pinfunction "CP_15") (pintype "input"))
    )
    (net (code "14") (name "CPU_F=0") (class "Default")
      (node (ref "R3") (pin "1") (pinfunction "1_1") (pintype "passive"))
      (node (ref "U58") (pin "11") (pinfunction "F=0_11") (pintype "output"))
      (node (ref "U59") (pin "11") (pinfunction "F=0_11") (pintype "output"))
    )
    (net (code "15") (name "CPU_I0") (class "Default")
      (node (ref "U58") (pin "12") (pinfunction "I0_12") (pintype "input"))
      (node (ref "U59") (pin "12") (pinfunction "I0_12") (pintype "input"))
    )
    (net (code "16") (name "CPU_I1") (class "Default")
      (node (ref "U58") (pin "13") (pinfunction "I1_13") (pintype "input"))
      (node (ref "U59") (pin "13") (pinfunction "I1_13") (pintype "input"))
    )
    (net (code "17") (name "CPU_I2") (class "Default")
      (node (ref "U58") (pin "14") (pinfunction "I2_14") (pintype "input"))
      (node (ref "U59") (pin "14") (pinfunction "I2_14") (pintype "input"))
    )
    (net (code "18") (name "CPU_I3") (class "Default")
      (node (ref "U58") (pin "26") (pinfunction "I3_26") (pintype "input"))
      (node (ref "U59") (pin "26") (pinfunction "I3_26") (pintype "input"))
    )
    (net (code "19") (name "CPU_I4") (class "Default")
      (node (ref "U58") (pin "28") (pinfunction "I4_28") (pintype "input"))
      (node (ref "U59") (pin "28") (pinfunction "I4_28") (pintype "input"))
    )
    (net (code "20") (name "CPU_I5") (class "Default")
      (node (ref "U58") (pin "27") (pinfunction "I5_27") (pintype "input"))
      (node (ref "U59") (pin "27") (pinfunction "I5_27") (pintype "input"))
    )
    (net (code "21") (name "CPU_I6") (class "Default")
      (node (ref "U58") (pin "5") (pinfunction "I6_5") (pintype "input"))
      (node (ref "U59") (pin "5") (pinfunction "I6_5") (pintype "input"))
    )
    (net (code "22") (name "CPU_I7") (class "Default")
      (node (ref "U58") (pin "7") (pinfunction "I7_7") (pintype "input"))
      (node (ref "U59") (pin "7") (pinfunction "I7_7") (pintype "input"))
    )
    (net (code "23") (name "CPU_I8") (class "Default")
      (node (ref "U58") (pin "6") (pinfunction "I8_6") (pintype "input"))
      (node (ref "U59") (pin "6") (pinfunction "I8_6") (pintype "input"))
    )
    (net (code "24") (name "CPU_U58-D0") (class "Default")
      (node (ref "U32") (pin "4") (pinfunction "1Y_4") (pintype "tri_state"))
      (node (ref "U44") (pin "3") (pinfunction "Y4_3") (pintype "tri_state"))
      (node (ref "U45") (pin "3") (pinfunction "Y4_3") (pintype "tri_state"))
      (node (ref "U58") (pin "25") (pinfunction "D0_25") (pintype "input"))
      (node (ref "U60") (pin "18") (pinfunction "Y1_18") (pintype "tri_state"))
      (node (ref "U7") (pin "2") (pinfunction "1Q_2") (pintype "tri_state"))
    )
    (net (code "25") (name "CPU_U58-D1") (class "Default")
      (node (ref "U32") (pin "7") (pinfunction "2Y_7") (pintype "tri_state"))
      (node (ref "U44") (pin "5") (pinfunction "Y3_5") (pintype "tri_state"))
      (node (ref "U45") (pin "5") (pinfunction "Y3_5") (pintype "tri_state"))
      (node (ref "U58") (pin "24") (pinfunction "D1_24") (pintype "input"))
      (node (ref "U60") (pin "16") (pinfunction "Y2_16") (pintype "tri_state"))
      (node (ref "U7") (pin "5") (pinfunction "2Q_5") (pintype "tri_state"))
    )
    (net (code "26") (name "CPU_U58-D2") (class "Default")
      (node (ref "U32") (pin "9") (pinfunction "3Y_9") (pintype "tri_state"))
      (node (ref "U44") (pin "7") (pinfunction "Y2_7") (pintype "tri_state"))
      (node (ref "U45") (pin "7") (pinfunction "Y2_7") (pintype "tri_state"))
      (node (ref "U58") (pin "23") (pinfunction "D2_23") (pintype "input"))
      (node (ref "U60") (pin "14") (pinfunction "Y3_14") (pintype "tri_state"))
      (node (ref "U7") (pin "6") (pinfunction "3Q_6") (pintype "tri_state"))
    )
    (net (code "27") (name "CPU_U58-D3") (class "Default")
      (node (ref "U32") (pin "12") (pinfunction "4Y_12") (pintype "tri_state"))
      (node (ref "U44") (pin "9") (pinfunction "Y1_9") (pintype "tri_state"))
      (node (ref "U45") (pin "9") (pinfunction "Y1_9") (pintype "tri_state"))
      (node (ref "U58") (pin "22") (pinfunction "D3_22") (pintype "input"))
      (node (ref "U60") (pin "12") (pinfunction "Y4_12") (pintype "tri_state"))
      (node (ref "U7") (pin "9") (pinfunction "4Q_9") (pintype "tri_state"))
    )
    (net (code "28") (name "CPU_U58-Y0") (class "Default")
      (node (ref "U39") (pin "3") (pinfunction "1D_3") (pintype "input"))
      (node (ref "U40") (pin "3") (pinfunction "1D_3") (pintype "input"))
      (node (ref "U58") (pin "36") (pinfunction "Y0_36") (pintype "output"))
      (node (ref "U68") (pin "5") (pinfunction "R0_5") (pintype "input"))
    )
    (net (code "29") (name "CPU_U58-Y1") (class "Default")
      (node (ref "U39") (pin "4") (pinfunction "2D_4") (pintype "input"))
      (node (ref "U40") (pin "4") (pinfunction "2D_4") (pintype "input"))
      (node (ref "U58") (pin "37") (pinfunction "Y1_37") (pintype "output"))
      (node (ref "U68") (pin "4") (pinfunction "R1_4") (pintype "input"))
    )
    (net (code "30") (name "CPU_U58-Y2") (class "Default")
      (node (ref "U39") (pin "7") (pinfunction "3D_7") (pintype "input"))
      (node (ref "U40") (pin "7") (pinfunction "3D_7") (pintype "input"))
      (node (ref "U58") (pin "38") (pinfunction "Y2_38") (pintype "output"))
      (node (ref "U68") (pin "3") (pinfunction "R2_3") (pintype "input"))
    )
    (net (code "31") (name "CPU_U58-Y3") (class "Default")
      (node (ref "U39") (pin "8") (pinfunction "4D_8") (pintype "input"))
      (node (ref "U40") (pin "8") (pinfunction "4D_8") (pintype "input"))
      (node (ref "U58") (pin "39") (pinfunction "Y3_39") (pintype "output"))
      (node (ref "U68") (pin "2") (pinfunction "R3_2") (pintype "input"))
    )
    (net (code "32") (name "CPU_U59-D0") (class "Default")
      (node (ref "U30") (pin "4") (pinfunction "1Y_4") (pintype "tri_state"))
      (node (ref "U44") (pin "12") (pinfunction "Y4_12") (pintype "tri_state"))
      (node (ref "U45") (pin "12") (pinfunction "Y4_12") (pintype "tri_state"))
      (node (ref "U59") (pin "25") (pinfunction "D0_25") (pintype "input"))
      (node (ref "U7") (pin "12") (pinfunction "5Q_12") (pintype "tri_state"))
    )
    (net (code "33") (name "CPU_U59-D1") (class "Default")
      (node (ref "U30") (pin "7") (pinfunction "2Y_7") (pintype "tri_state"))
      (node (ref "U44") (pin "14") (pinfunction "Y3_14") (pintype "tri_state"))
      (node (ref "U45") (pin "14") (pinfunction "Y3_14") (pintype "tri_state"))
      (node (ref "U59") (pin "24") (pinfunction "D1_24") (pintype "input"))
      (node (ref "U7") (pin "15") (pinfunction "6Q_15") (pintype "tri_state"))
    )
    (net (code "34") (name "CPU_U59-D2") (class "Default")
      (node (ref "U30") (pin "9") (pinfunction "3Y_9") (pintype "tri_state"))
      (node (ref "U44") (pin "16") (pinfunction "Y2_16") (pintype "tri_state"))
      (node (ref "U45") (pin "16") (pinfunction "Y2_16") (pintype "tri_state"))
      (node (ref "U59") (pin "23") (pinfunction "D2_23") (pintype "input"))
      (node (ref "U7") (pin "16") (pinfunction "7Q_16") (pintype "tri_state"))
    )
    (net (code "35") (name "CPU_U59-D3") (class "Default")
      (node (ref "U30") (pin "12") (pinfunction "4Y_12") (pintype "tri_state"))
      (node (ref "U44") (pin "18") (pinfunction "Y1_18") (pintype "tri_state"))
      (node (ref "U45") (pin "18") (pinfunction "Y1_18") (pintype "tri_state"))
      (node (ref "U59") (pin "22") (pinfunction "D3_22") (pintype "input"))
      (node (ref "U7") (pin "19") (pinfunction "8Q_19") (pintype "tri_state"))
    )
    (net (code "36") (name "CPU_U59-Y0") (class "Default")
      (node (ref "U39") (pin "13") (pinfunction "5D_13") (pintype "input"))
      (node (ref "U40") (pin "13") (pinfunction "5D_13") (pintype "input"))
      (node (ref "U59") (pin "36") (pinfunction "Y0_36") (pintype "output"))
      (node (ref "U67") (pin "5") (pinfunction "R0_5") (pintype "input"))
    )
    (net (code "37") (name "CPU_U59-Y1") (class "Default")
      (node (ref "U39") (pin "14") (pinfunction "6D_14") (pintype "input"))
      (node (ref "U59") (pin "37") (pinfunction "Y1_37") (pintype "output"))
      (node (ref "U67") (pin "4") (pinfunction "R1_4") (pintype "input"))
    )
    (net (code "38") (name "CPU_U59-Y2") (class "Default")
      (node (ref "U39") (pin "17") (pinfunction "7D_17") (pintype "input"))
      (node (ref "U40") (pin "17") (pinfunction "7D_17") (pintype "input"))
      (node (ref "U59") (pin "38") (pinfunction "Y2_38") (pintype "output"))
      (node (ref "U67") (pin "3") (pinfunction "R2_3") (pintype "input"))
    )
    (net (code "39") (name "CPU_U59-Y3") (class "Default")
      (node (ref "U39") (pin "18") (pinfunction "8D_18") (pintype "input"))
      (node (ref "U40") (pin "18") (pinfunction "8D_18") (pintype "input"))
      (node (ref "U59") (pin "39") (pinfunction "Y3_39") (pintype "output"))
      (node (ref "U67") (pin "2") (pinfunction "R3_2") (pintype "input"))
    )
    (net (code "40") (name "CPU_~{OE}") (class "Default")
      (node (ref "U58") (pin "40") (pinfunction "~{OE}_40") (pintype "input"))
      (node (ref "U59") (pin "40") (pinfunction "~{OE}_40") (pintype "input"))
    )
    (net (code "41") (name "GND") (class "Default")
      (node (ref "C15") (pin "2") (pinfunction "2_2") (pintype "passive"))
      (node (ref "C16") (pin "2") (pinfunction "2_2") (pintype "passive"))
      (node (ref "C17") (pin "2") (pinfunction "2_2") (pintype "passive"))
      (node (ref "C19") (pin "2") (pinfunction "2_2") (pintype "passive"))
      (node (ref "C21") (pin "2") (pinfunction "2_2") (pintype "passive"))
      (node (ref "C22") (pin "2") (pinfunction "2_2") (pintype "passive"))
      (node (ref "C23") (pin "2") (pinfunction "2_2") (pintype "passive"))
      (node (ref "C24") (pin "2") (pinfunction "2_2") (pintype "passive"))
      (node (ref "C26") (pin "2") (pinfunction "2_2") (pintype "passive"))
      (node (ref "C28") (pin "2") (pinfunction "2_2") (pintype "passive"))
      (node (ref "C31") (pin "2") (pinfunction "2_2") (pintype "passive"))
      (node (ref "C32") (pin "2") (pinfunction "2_2") (pintype "passive"))
      (node (ref "C33") (pin "2") (pinfunction "2_2") (pintype "passive"))
      (node (ref "C34") (pin "2") (pinfunction "2_2") (pintype "passive"))
      (node (ref "C36") (pin "2") (pinfunction "2_2") (pintype "passive"))
      (node (ref "C41") (pin "2") (pinfunction "2_2") (pintype "passive"))
      (node (ref "C47") (pin "1") (pinfunction "1_1") (pintype "passive"))
      (node (ref "C5") (pin "2") (pinfunction "2_2") (pintype "passive"))
      (node (ref "C53") (pin "2") (pinfunction "2_2") (pintype "passive"))
      (node (ref "C54") (pin "2") (pinfunction "2_2") (pintype "passive"))
      (node (ref "C6") (pin "2") (pinfunction "2_2") (pintype "passive"))
      (node (ref "P1") (pin "11A") (pinfunction "11A_11A") (pintype "passive"))
      (node (ref "P1") (pin "1A") (pinfunction "1A_1A") (pintype "passive"))
      (node (ref "P1") (pin "1B") (pinfunction "1B_1B") (pintype "passive"))
      (node (ref "P1") (pin "20A") (pinfunction "20A_20A") (pintype "passive"))
      (node (ref "P1") (pin "20B") (pinfunction "20B_20B") (pintype "passive"))
      (node (ref "P1") (pin "21B") (pinfunction "1B_21B") (pintype "passive"))
      (node (ref "P1") (pin "22B") (pinfunction "2B_22B") (pintype "passive"))
      (node (ref "P1") (pin "23B") (pinfunction "3B_23B") (pintype "passive"))
      (node (ref "P1") (pin "24A") (pinfunction "4A_24A") (pintype "passive"))
      (node (ref "P1") (pin "25A") (pinfunction "5A_25A") (pintype "passive"))
      (node (ref "P1") (pin "41A") (pinfunction "1A_41A") (pintype "passive"))
      (node (ref "P1") (pin "51A") (pinfunction "11A_51A") (pintype "passive"))
      (node (ref "P1") (pin "51B") (pinfunction "11B_51B") (pintype "passive"))
      (node (ref "P1") (pin "5A") (pinfunction "5A_5A") (pintype "passive"))
      (node (ref "P1") (pin "5B") (pinfunction "5B_5B") (pintype "passive"))
      (node (ref "P1") (pin "61A") (pinfunction "1A_61A") (pintype "passive"))
      (node (ref "P1") (pin "61B") (pinfunction "1B_61B") (pintype "passive"))
      (node (ref "P1") (pin "71A") (pinfunction "11A_71A") (pintype "passive"))
      (node (ref "P1") (pin "7A") (pinfunction "7A_7A") (pintype "passive"))
      (node (ref "P1") (pin "7B") (pinfunction "7B_7B") (pintype "passive"))
      (node (ref "P1") (pin "80A") (pinfunction "20A_80A") (pintype "passive"))
      (node (ref "P1") (pin "9A") (pinfunction "9A_9A") (pintype "passive"))
      (node (ref "P1") (pin "9B") (pinfunction "9B_9B") (pintype "passive"))
      (node (ref "RN2") (pin "8") (pinfunction "B_8") (pintype "passive"))
      (node (ref "U20") (pin "8") (pinfunction "~{CE1}_8") (pintype "input"))
      (node (ref "U20") (pin "9") (pinfunction "GND_9") (pintype "power_in"))
      (node (ref "U21") (pin "8") (pinfunction "~{CE1}_8") (pintype "input"))
      (node (ref "U21") (pin "9") (pinfunction "GND_9") (pintype "power_in"))
      (node (ref "U22") (pin "8") (pinfunction "~{CE1}_8") (pintype "input"))
      (node (ref "U22") (pin "9") (pinfunction "GND_9") (pintype "power_in"))
      (node (ref "U23") (pin "8") (pinfunction "~{CE1}_8") (pintype "input"))
      (node (ref "U23") (pin "9") (pinfunction "GND_9") (pintype "power_in"))
      (node (ref "U24") (pin "8") (pinfunction "~{CE1}_8") (pintype "input"))
      (node (ref "U24") (pin "9") (pinfunction "GND_9") (pintype "power_in"))
      (node (ref "U25") (pin "8") (pinfunction "~{CE1}_8") (pintype "input"))
      (node (ref "U25") (pin "9") (pinfunction "GND_9") (pintype "power_in"))
      (node (ref "U26") (pin "8") (pinfunction "~{CE1}_8") (pintype "input"))
      (node (ref "U26") (pin "9") (pinfunction "GND_9") (pintype "power_in"))
      (node (ref "U27") (pin "1") (pinfunction "I0_1") (pintype "input"))
      (node (ref "U27") (pin "7") (pinfunction "GND_7") (pintype "power_in"))
      (node (ref "U28") (pin "12") (pinfunction "I0_12") (pintype "input"))
      (node (ref "U28") (pin "7") (pinfunction "GND_7") (pintype "power_in"))
      (node (ref "U30") (pin "8") (pinfunction "GND_8") (pintype "power_in"))
      (node (ref "U31") (pin "8") (pinfunction "GND_8") (pintype "power_in"))
      (node (ref "U32") (pin "8") (pinfunction "GND_8") (pintype "power_in"))
      (node (ref "U34") (pin "15") (pinfunction "G_15") (pintype "input"))
      (node (ref "U34") (pin "8") (pinfunction "GND_8") (pintype "power_in"))
      (node (ref "U39") (pin "10") (pinfunction "GND_10") (pintype "power_in"))
      (node (ref "U40") (pin "10") (pinfunction "GND_10") (pintype "power_in"))
      (node (ref "U43") (pin "10") (pinfunction "GND_10") (pintype "power_in"))
      (node (ref "U44") (pin "10") (pinfunction "GND_10") (pintype "power_in"))
      (node (ref "U44") (pin "2") (pinfunction "A1_2") (pintype "input"))
      (node (ref "U45") (pin "10") (pinfunction "GND_10") (pintype "power_in"))
      (node (ref "U46") (pin "10") (pinfunction "GND_10") (pintype "power_in"))
      (node (ref "U49") (pin "8") (pinfunction "GND_8") (pintype "power_in"))
      (node (ref "U5") (pin "7") (pinfunction "GND_7") (pintype "power_in"))
      (node (ref "U53") (pin "4") (pinfunction "G2A_4") (pintype "input"))
      (node (ref "U53") (pin "8") (pinfunction "GND_8") (pintype "power_in"))
      (node (ref "U56") (pin "7") (pinfunction "GND_7") (pintype "power_in"))
      (node (ref "U57") (pin "7") (pinfunction "GND_7") (pintype "power_in"))
      (node (ref "U58") (pin "30") (pinfunction "GND_30") (pintype "power_in"))
      (node (ref "U59") (pin "30") (pinfunction "GND_30") (pintype "power_in"))
      (node (ref "U60") (pin "10") (pinfunction "GND_10") (pintype "power_in"))
      (node (ref "U67") (pin "10") (pinfunction "OR1_10") (pintype "input"))
      (node (ref "U67") (pin "12") (pinfunction "OR0_12") (pintype "input"))
      (node (ref "U67") (pin "14") (pinfunction "GND_14") (pintype "power_in"))
      (node (ref "U67") (pin "6") (pinfunction "OR3_6") (pintype "input"))
      (node (ref "U67") (pin "8") (pinfunction "OR2_8") (pintype "input"))
      (node (ref "U68") (pin "10") (pinfunction "OR1_10") (pintype "input"))
      (node (ref "U68") (pin "12") (pinfunction "OR0_12") (pintype "input"))
      (node (ref "U68") (pin "14") (pinfunction "GND_14") (pintype "power_in"))
      (node (ref "U68") (pin "6") (pinfunction "OR3_6") (pintype "input"))
      (node (ref "U68") (pin "8") (pinfunction "OR2_8") (pintype "input"))
      (node (ref "U7") (pin "10") (pinfunction "GND_10") (pintype "power_in"))
    )
    (net (code "42") (name "IO41B") (class "Default")
      (node (ref "P1") (pin "41B") (pinfunction "1B_41B") (pintype "passive"))
      (node (ref "RN2") (pin "13") (pinfunction "R12_13") (pintype "passive"))
      (node (ref "U44") (pin "17") (pinfunction "A4_17") (pintype "input"))
    )
    (net (code "43") (name "IO42A") (class "Default")
      (node (ref "P1") (pin "42A") (pinfunction "2A_42A") (pintype "passive"))
      (node (ref "RN2") (pin "11") (pinfunction "R10_11") (pintype "passive"))
      (node (ref "U44") (pin "15") (pinfunction "A3_15") (pintype "input"))
    )
    (net (code "44") (name "IO42B") (class "Default")
      (node (ref "P1") (pin "42B") (pinfunction "2B_42B") (pintype "passive"))
      (node (ref "RN2") (pin "9") (pinfunction "R8_9") (pintype "passive"))
      (node (ref "U44") (pin "13") (pinfunction "A2_13") (pintype "input"))
    )
    (net (code "45") (name "IO43A") (class "Default")
      (node (ref "P1") (pin "43A") (pinfunction "3A_43A") (pintype "passive"))
      (node (ref "RN2") (pin "12") (pinfunction "R11_12") (pintype "passive"))
      (node (ref "U44") (pin "11") (pinfunction "A1_11") (pintype "input"))
    )
    (net (code "46") (name "IO43B") (class "Default")
      (node (ref "P1") (pin "43B") (pinfunction "3B_43B") (pintype "passive"))
      (node (ref "RN2") (pin "10") (pinfunction "R9_10") (pintype "passive"))
      (node (ref "U44") (pin "8") (pinfunction "A4_8") (pintype "input"))
    )
    (net (code "47") (name "IO44A") (class "Default")
      (node (ref "P1") (pin "44A") (pinfunction "4A_44A") (pintype "passive"))
      (node (ref "RN2") (pin "7") (pinfunction "R7_7") (pintype "passive"))
      (node (ref "U44") (pin "6") (pinfunction "A3_6") (pintype "input"))
    )
    (net (code "48") (name "IO44B") (class "Default")
      (node (ref "P1") (pin "44B") (pinfunction "4B_44B") (pintype "passive"))
      (node (ref "U32") (pin "13") (pinfunction "4B_13") (pintype "input"))
      (node (ref "U40") (pin "9") (pinfunction "4Q_9") (pintype "tri_state"))
    )
    (net (code "49") (name "IO45A") (class "Default")
      (node (ref "P1") (pin "45A") (pinfunction "5A_45A") (pintype "passive"))
      (node (ref "U40") (pin "15") (pinfunction "6Q_15") (pintype "tri_state"))
    )
    (net (code "50") (name "IO45B") (class "Default")
      (node (ref "P1") (pin "45B") (pinfunction "5B_45B") (pintype "passive"))
    )
    (net (code "51") (name "IO46A") (class "Default")
      (node (ref "P1") (pin "46A") (pinfunction "6A_46A") (pintype "passive"))
      (node (ref "U32") (pin "6") (pinfunction "2B_6") (pintype "input"))
      (node (ref "U40") (pin "5") (pinfunction "2Q_5") (pintype "tri_state"))
    )
    (net (code "52") (name "IO46B") (class "Default")
      (node (ref "P1") (pin "46B") (pinfunction "6B_46B") (pintype "passive"))
      (node (ref "U32") (pin "10") (pinfunction "3B_10") (pintype "input"))
      (node (ref "U40") (pin "6") (pinfunction "3Q_6") (pintype "tri_state"))
    )
    (net (code "53") (name "IO47A") (class "Default")
      (node (ref "P1") (pin "47A") (pinfunction "7A_47A") (pintype "passive"))
      (node (ref "U40") (pin "12") (pinfunction "5Q_12") (pintype "tri_state"))
    )
    (net (code "54") (name "IO47B") (class "Default")
      (node (ref "P1") (pin "47B") (pinfunction "7B_47B") (pintype "passive"))
      (node (ref "U40") (pin "16") (pinfunction "7Q_16") (pintype "tri_state"))
    )
    (net (code "55") (name "IO52A") (class "Default")
      (node (ref "P1") (pin "52A") (pinfunction "12A_52A") (pintype "passive"))
      (node (ref "RN2") (pin "6") (pinfunction "R6_6") (pintype "passive"))
      (node (ref "U44") (pin "4") (pinfunction "A2_4") (pintype "input"))
    )
    (net (code "56") (name "IO54A-BUSA-PARITY") (class "Default")
      (node (ref "P1") (pin "54A") (pinfunction "14A_54A") (pintype "passive"))
      (node (ref "U31") (pin "14") (pinfunction "4A_14") (pintype "input"))
      (node (ref "U57") (pin "5") (pinfunction "SEV_5") (pintype "output"))
    )
    (net (code "57") (name "IO54A-BUSA7") (class "Default")
      (node (ref "P1") (pin "54B") (pinfunction "14B_54B") (pintype "passive"))
      (node (ref "U39") (pin "19") (pinfunction "8Q_19") (pintype "tri_state"))
      (node (ref "U43") (pin "17") (pinfunction "A4_17") (pintype "input"))
      (node (ref "U57") (pin "2") (pinfunction "H_2") (pintype "input"))
    )
    (net (code "58") (name "IO55A-BUSA6") (class "Default")
      (node (ref "P1") (pin "55A") (pinfunction "15A_55A") (pintype "passive"))
      (node (ref "U39") (pin "16") (pinfunction "7Q_16") (pintype "tri_state"))
      (node (ref "U43") (pin "15") (pinfunction "A3_15") (pintype "input"))
      (node (ref "U57") (pin "1") (pinfunction "G_1") (pintype "input"))
    )
    (net (code "59") (name "IO55B-BUSA5") (class "Default")
      (node (ref "P1") (pin "55B") (pinfunction "15B_55B") (pintype "passive"))
      (node (ref "U39") (pin "15") (pinfunction "6Q_15") (pintype "tri_state"))
      (node (ref "U43") (pin "13") (pinfunction "A2_13") (pintype "input"))
      (node (ref "U57") (pin "13") (pinfunction "F_13") (pintype "input"))
    )
    (net (code "60") (name "IO56A-BUSA4") (class "Default")
      (node (ref "P1") (pin "56A") (pinfunction "16A_56A") (pintype "passive"))
      (node (ref "U39") (pin "12") (pinfunction "5Q_12") (pintype "tri_state"))
      (node (ref "U43") (pin "11") (pinfunction "A1_11") (pintype "input"))
      (node (ref "U57") (pin "12") (pinfunction "E_12") (pintype "input"))
    )
    (net (code "61") (name "IO56B-BUSA3") (class "Default")
      (node (ref "P1") (pin "56B") (pinfunction "16B_56B") (pintype "passive"))
      (node (ref "U39") (pin "9") (pinfunction "4Q_9") (pintype "tri_state"))
      (node (ref "U43") (pin "8") (pinfunction "A4_8") (pintype "input"))
      (node (ref "U57") (pin "11") (pinfunction "D_11") (pintype "input"))
    )
    (net (code "62") (name "IO57A-BUSA2") (class "Default")
      (node (ref "P1") (pin "57A") (pinfunction "17A_57A") (pintype "passive"))
      (node (ref "U39") (pin "6") (pinfunction "3Q_6") (pintype "tri_state"))
      (node (ref "U43") (pin "6") (pinfunction "A3_6") (pintype "input"))
      (node (ref "U57") (pin "10") (pinfunction "C_10") (pintype "input"))
    )
    (net (code "63") (name "IO57B-BUSA1") (class "Default")
      (node (ref "P1") (pin "57B") (pinfunction "17B_57B") (pintype "passive"))
      (node (ref "U39") (pin "5") (pinfunction "2Q_5") (pintype "tri_state"))
      (node (ref "U43") (pin "4") (pinfunction "A2_4") (pintype "input"))
      (node (ref "U57") (pin "9") (pinfunction "B_9") (pintype "input"))
    )
    (net (code "64") (name "IO58A-BUSA0") (class "Default")
      (node (ref "P1") (pin "58A") (pinfunction "18A_58A") (pintype "passive"))
      (node (ref "U39") (pin "2") (pinfunction "1Q_2") (pintype "tri_state"))
      (node (ref "U43") (pin "2") (pinfunction "A1_2") (pintype "input"))
      (node (ref "U57") (pin "8") (pinfunction "A_8") (pintype "input"))
    )
    (net (code "65") (name "IO62A") (class "Default")
      (node (ref "P1") (pin "62A") (pinfunction "2A_62A") (pintype "passive"))
      (node (ref "RN1") (pin "6") (pinfunction "R6_6") (pintype "passive"))
      (node (ref "U5") (pin "11") (pinfunction "I_11") (pintype "input"))
    )
    (net (code "66") (name "IO62B") (class "Default")
      (node (ref "P1") (pin "62B") (pinfunction "2B_62B") (pintype "passive"))
      (node (ref "RN1") (pin "11") (pinfunction "R10_11") (pintype "passive"))
      (node (ref "U5") (pin "9") (pinfunction "I_9") (pintype "input"))
    )
    (net (code "67") (name "IO63A") (class "Default")
      (node (ref "P1") (pin "63A") (pinfunction "3A_63A") (pintype "passive"))
      (node (ref "RN2") (pin "15") (pinfunction "R14_15") (pintype "passive"))
      (node (ref "U46") (pin "17") (pinfunction "A4_17") (pintype "input"))
    )
    (net (code "68") (name "IO63B") (class "Default")
      (node (ref "P1") (pin "63B") (pinfunction "3B_63B") (pintype "passive"))
      (node (ref "RN2") (pin "1") (pinfunction "R1_1") (pintype "passive"))
      (node (ref "U46") (pin "15") (pinfunction "A3_15") (pintype "input"))
    )
    (net (code "69") (name "IO64A") (class "Default")
      (node (ref "P1") (pin "64A") (pinfunction "4A_64A") (pintype "passive"))
      (node (ref "RN2") (pin "2") (pinfunction "R2_2") (pintype "passive"))
      (node (ref "U46") (pin "13") (pinfunction "A2_13") (pintype "input"))
    )
    (net (code "70") (name "IO64B") (class "Default")
      (node (ref "P1") (pin "64B") (pinfunction "4B_64B") (pintype "passive"))
      (node (ref "RN2") (pin "14") (pinfunction "R13_14") (pintype "passive"))
      (node (ref "U46") (pin "11") (pinfunction "A1_11") (pintype "input"))
    )
    (net (code "71") (name "IO65A") (class "Default")
      (node (ref "RN2") (pin "3") (pinfunction "R3_3") (pintype "passive"))
      (node (ref "U46") (pin "8") (pinfunction "A4_8") (pintype "input"))
    )
    (net (code "72") (name "IO65B") (class "Default")
      (node (ref "P1") (pin "65B") (pinfunction "5B_65B") (pintype "passive"))
      (node (ref "RN2") (pin "5") (pinfunction "R5_5") (pintype "passive"))
      (node (ref "U46") (pin "6") (pinfunction "A3_6") (pintype "input"))
    )
    (net (code "73") (name "IO66A") (class "Default")
      (node (ref "P1") (pin "66A") (pinfunction "6A_66A") (pintype "passive"))
      (node (ref "RN2") (pin "4") (pinfunction "R4_4") (pintype "passive"))
      (node (ref "U46") (pin "4") (pinfunction "A2_4") (pintype "input"))
    )
    (net (code "74") (name "IO66B") (class "Default")
      (node (ref "P1") (pin "66B") (pinfunction "6B_66B") (pintype "passive"))
      (node (ref "RN1") (pin "2") (pinfunction "R2_2") (pintype "passive"))
      (node (ref "U46") (pin "2") (pinfunction "A1_2") (pintype "input"))
    )
    (net (code "75") (name "IO67A") (class "Default")
      (node (ref "P1") (pin "67A") (pinfunction "7A_67A") (pintype "passive"))
      (node (ref "RN1") (pin "13") (pinfunction "R12_13") (pintype "passive"))
      (node (ref "U45") (pin "4") (pinfunction "A2_4") (pintype "input"))
    )
    (net (code "76") (name "IO67B") (class "Default")
      (node (ref "P1") (pin "67B") (pinfunction "7B_67B") (pintype "passive"))
      (node (ref "RN1") (pin "9") (pinfunction "R8_9") (pintype "passive"))
      (node (ref "U45") (pin "8") (pinfunction "A4_8") (pintype "input"))
    )
    (net (code "77") (name "IO68A") (class "Default")
      (node (ref "P1") (pin "68A") (pinfunction "8A_68A") (pintype "passive"))
      (node (ref "RN1") (pin "3") (pinfunction "R3_3") (pintype "passive"))
      (node (ref "U45") (pin "11") (pinfunction "A1_11") (pintype "input"))
    )
    (net (code "78") (name "IO68B") (class "Default")
      (node (ref "P1") (pin "68B") (pinfunction "8B_68B") (pintype "passive"))
      (node (ref "RN1") (pin "10") (pinfunction "R9_10") (pintype "passive"))
      (node (ref "U45") (pin "6") (pinfunction "A3_6") (pintype "input"))
    )
    (net (code "79") (name "IO69A") (class "Default")
      (node (ref "P1") (pin "69A") (pinfunction "9A_69A") (pintype "passive"))
      (node (ref "RN1") (pin "12") (pinfunction "R11_12") (pintype "passive"))
      (node (ref "U45") (pin "2") (pinfunction "A1_2") (pintype "input"))
    )
    (net (code "80") (name "IO69B") (class "Default")
      (node (ref "P1") (pin "69B") (pinfunction "9B_69B") (pintype "passive"))
      (node (ref "RN1") (pin "7") (pinfunction "R7_7") (pintype "passive"))
      (node (ref "U5") (pin "13") (pinfunction "I_13") (pintype "input"))
    )
    (net (code "81") (name "IO72A") (class "Default")
      (node (ref "P1") (pin "72A") (pinfunction "12A_72A") (pintype "passive"))
      (node (ref "U5") (pin "1") (pinfunction "I_1") (pintype "input"))
    )
    (net (code "82") (name "IO75A") (class "Default")
      (node (ref "P1") (pin "75A") (pinfunction "15A_75A") (pintype "passive"))
      (node (ref "U5") (pin "4") (pinfunction "O_4") (pintype "output"))
    )
    (net (code "83") (name "IO76A") (class "Default")
      (node (ref "P1") (pin "76A") (pinfunction "16A_76A") (pintype "passive"))
      (node (ref "R1") (pin "1") (pinfunction "1_1") (pintype "passive"))
      (node (ref "U5") (pin "6") (pinfunction "O_6") (pintype "output"))
    )
    (net (code "84") (name "IO_MAD12") (class "Default")
      (node (ref "P1") (pin "31A") (pinfunction "11A_31A") (pintype "passive"))
      (node (ref "U28") (pin "1") (pinfunction "I0_1") (pintype "input"))
    )
    (net (code "85") (name "IO_MAD13") (class "Default")
      (node (ref "P1") (pin "31B") (pinfunction "11B_31B") (pintype "passive"))
      (node (ref "R17") (pin "2") (pinfunction "2_2") (pintype "passive"))
      (node (ref "U28") (pin "4") (pinfunction "I0_4") (pintype "input"))
    )
    (net (code "86") (name "IO_MAD14") (class "Default")
      (node (ref "P1") (pin "32A") (pinfunction "12A_32A") (pintype "passive"))
      (node (ref "R18") (pin "2") (pinfunction "2_2") (pintype "passive"))
      (node (ref "U28") (pin "10") (pinfunction "I1_10") (pintype "input"))
      (node (ref "U30") (pin "3") (pinfunction "1B_3") (pintype "input"))
    )
    (net (code "87") (name "IO_MAD15") (class "Default")
      (node (ref "P1") (pin "32B") (pinfunction "12B_32B") (pintype "passive"))
      (node (ref "R19") (pin "2") (pinfunction "2_2") (pintype "passive"))
      (node (ref "U27") (pin "4") (pinfunction "I0_4") (pintype "input"))
      (node (ref "U30") (pin "6") (pinfunction "2B_6") (pintype "input"))
    )
    (net (code "88") (name "IO_~{AD00}") (class "Default")
      (node (ref "P1") (pin "12A") (pinfunction "12A_12A") (pintype "passive"))
    )
    (net (code "89") (name "IO_~{AD01}") (class "Default")
      (node (ref "P1") (pin "12B") (pinfunction "12B_12B") (pintype "passive"))
    )
    (net (code "90") (name "IO_~{AD02}") (class "Default")
      (node (ref "P1") (pin "13A") (pinfunction "13A_13A") (pintype "passive"))
    )
    (net (code "91") (name "IO_~{AD03}") (class "Default")
      (node (ref "P1") (pin "13B") (pinfunction "13B_13B") (pintype "passive"))
    )
    (net (code "92") (name "IO_~{AD04}") (class "Default")
      (node (ref "P1") (pin "14A") (pinfunction "14A_14A") (pintype "passive"))
    )
    (net (code "93") (name "IO_~{AD05}") (class "Default")
      (node (ref "P1") (pin "14B") (pinfunction "14B_14B") (pintype "passive"))
    )
    (net (code "94") (name "IO_~{AD06}") (class "Default")
      (node (ref "P1") (pin "15A") (pinfunction "15A_15A") (pintype "passive"))
    )
    (net (code "95") (name "IO_~{AD07}") (class "Default")
      (node (ref "P1") (pin "15B") (pinfunction "15B_15B") (pintype "passive"))
    )
    (net (code "96") (name "IO_~{AD08}") (class "Default")
      (node (ref "P1") (pin "16A") (pinfunction "16A_16A") (pintype "passive"))
    )
    (net (code "97") (name "IO_~{AD09}") (class "Default")
      (node (ref "P1") (pin "16B") (pinfunction "16B_16B") (pintype "passive"))
    )
    (net (code "98") (name "IO_~{AD10}") (class "Default")
      (node (ref "P1") (pin "17A") (pinfunction "17A_17A") (pintype "passive"))
      (node (ref "U28") (pin "13") (pinfunction "I1_13") (pintype "input"))
    )
    (net (code "99") (name "IO_~{AD11}") (class "Default")
      (node (ref "P1") (pin "17B") (pinfunction "17B_17B") (pintype "passive"))
      (node (ref "U27") (pin "2") (pinfunction "I1_2") (pintype "input"))
    )
    (net (code "100") (name "IO_~{AD12}") (class "Default")
      (node (ref "P1") (pin "18A") (pinfunction "18A_18A") (pintype "passive"))
      (node (ref "U28") (pin "2") (pinfunction "I1_2") (pintype "input"))
    )
    (net (code "101") (name "IO_~{AD13}") (class "Default")
      (node (ref "P1") (pin "18B") (pinfunction "18B_18B") (pintype "passive"))
      (node (ref "U28") (pin "5") (pinfunction "I1_5") (pintype "input"))
    )
    (net (code "102") (name "IO_~{AD14}") (class "Default")
      (node (ref "P1") (pin "19A") (pinfunction "19A_19A") (pintype "passive"))
      (node (ref "U28") (pin "9") (pinfunction "I0_9") (pintype "input"))
    )
    (net (code "103") (name "IO_~{AD15}") (class "Default")
      (node (ref "P1") (pin "19B") (pinfunction "19B_19B") (pintype "passive"))
      (node (ref "U27") (pin "5") (pinfunction "I1_5") (pintype "input"))
    )
    (net (code "104") (name "IO_~{DAT0}") (class "Default")
      (node (ref "P1") (pin "26A") (pinfunction "6A_26A") (pintype "passive"))
      (node (ref "U7") (pin "3") (pinfunction "1D_3") (pintype "input"))
    )
    (net (code "105") (name "IO_~{DAT1}") (class "Default")
      (node (ref "P1") (pin "26B") (pinfunction "6B_26B") (pintype "passive"))
      (node (ref "U7") (pin "4") (pinfunction "2D_4") (pintype "input"))
    )
    (net (code "106") (name "IO_~{DAT2}") (class "Default")
      (node (ref "P1") (pin "27A") (pinfunction "7A_27A") (pintype "passive"))
      (node (ref "U7") (pin "7") (pinfunction "3D_7") (pintype "input"))
    )
    (net (code "107") (name "IO_~{DAT3}") (class "Default")
      (node (ref "P1") (pin "27B") (pinfunction "7B_27B") (pintype "passive"))
      (node (ref "U7") (pin "8") (pinfunction "4D_8") (pintype "input"))
    )
    (net (code "108") (name "IO_~{DAT4}") (class "Default")
      (node (ref "P1") (pin "28A") (pinfunction "8A_28A") (pintype "passive"))
      (node (ref "U30") (pin "2") (pinfunction "1A_2") (pintype "input"))
      (node (ref "U7") (pin "13") (pinfunction "5D_13") (pintype "input"))
    )
    (net (code "109") (name "IO_~{DAT5}") (class "Default")
      (node (ref "P1") (pin "28B") (pinfunction "8B_28B") (pintype "passive"))
      (node (ref "U30") (pin "5") (pinfunction "2A_5") (pintype "input"))
      (node (ref "U7") (pin "14") (pinfunction "6D_14") (pintype "input"))
    )
    (net (code "110") (name "IO_~{DAT6}") (class "Default")
      (node (ref "P1") (pin "29A") (pinfunction "9A_29A") (pintype "passive"))
      (node (ref "U30") (pin "11") (pinfunction "3A_11") (pintype "input"))
      (node (ref "U7") (pin "17") (pinfunction "7D_17") (pintype "input"))
    )
    (net (code "111") (name "IO_~{DAT7}") (class "Default")
      (node (ref "P1") (pin "29B") (pinfunction "9B_29B") (pintype "passive"))
      (node (ref "U30") (pin "14") (pinfunction "4A_14") (pintype "input"))
      (node (ref "U7") (pin "18") (pinfunction "8D_18") (pintype "input"))
    )
    (net (code "112") (name "Net-(DS1-C)") (class "Default")
      (node (ref "C47") (pin "2") (pinfunction "2_2") (pintype "passive"))
      (node (ref "DS1") (pin "K") (pinfunction "C_K") (pintype "passive"))
      (node (ref "R21") (pin "1") (pinfunction "1_1") (pintype "passive"))
    )
    (net (code "113") (name "Net-(DS1-PadA)") (class "Default")
      (node (ref "DS1") (pin "A") (pinfunction "A_A") (pintype "passive"))
      (node (ref "R22") (pin "2") (pinfunction "2_2") (pintype "passive"))
    )
    (net (code "114") (name "Net-(U49A-CLR)") (class "Default")
      (node (ref "R13") (pin "1") (pinfunction "1_1") (pintype "passive"))
      (node (ref "U49") (pin "1") (pinfunction "CLR_1") (pintype "input"))
    )
    (net (code "115") (name "Net-(U49A-J)") (class "Default")
      (node (ref "U49") (pin "2") (pinfunction "J_2") (pintype "input"))
      (node (ref "U5") (pin "12") (pinfunction "O_12") (pintype "output"))
    )
    (net (code "116") (name "ROM_ADDR0") (class "Default")
      (node (ref "U20") (pin "5") (pinfunction "A0_5") (pintype "input"))
      (node (ref "U21") (pin "5") (pinfunction "A0_5") (pintype "input"))
      (node (ref "U22") (pin "5") (pinfunction "A0_5") (pintype "input"))
      (node (ref "U23") (pin "5") (pinfunction "A0_5") (pintype "input"))
      (node (ref "U24") (pin "5") (pinfunction "A0_5") (pintype "input"))
      (node (ref "U25") (pin "5") (pinfunction "A0_5") (pintype "input"))
      (node (ref "U26") (pin "5") (pinfunction "A0_5") (pintype "input"))
    )
    (net (code "117") (name "ROM_ADDR1") (class "Default")
      (node (ref "U20") (pin "6") (pinfunction "A1_6") (pintype "input"))
      (node (ref "U21") (pin "6") (pinfunction "A1_6") (pintype "input"))
      (node (ref "U22") (pin "6") (pinfunction "A1_6") (pintype "input"))
      (node (ref "U23") (pin "6") (pinfunction "A1_6") (pintype "input"))
      (node (ref "U24") (pin "6") (pinfunction "A1_6") (pintype "input"))
      (node (ref "U25") (pin "6") (pinfunction "A1_6") (pintype "input"))
      (node (ref "U26") (pin "6") (pinfunction "A1_6") (pintype "input"))
    )
    (net (code "118") (name "ROM_ADDR2") (class "Default")
      (node (ref "U20") (pin "7") (pinfunction "A2_7") (pintype "input"))
      (node (ref "U21") (pin "7") (pinfunction "A2_7") (pintype "input"))
      (node (ref "U22") (pin "7") (pinfunction "A2_7") (pintype "input"))
      (node (ref "U23") (pin "7") (pinfunction "A2_7") (pintype "input"))
      (node (ref "U24") (pin "7") (pinfunction "A2_7") (pintype "input"))
      (node (ref "U25") (pin "7") (pinfunction "A2_7") (pintype "input"))
      (node (ref "U26") (pin "7") (pinfunction "A2_7") (pintype "input"))
    )
    (net (code "119") (name "ROM_ADDR3") (class "Default")
      (node (ref "U20") (pin "4") (pinfunction "A3_4") (pintype "input"))
      (node (ref "U21") (pin "4") (pinfunction "A3_4") (pintype "input"))
      (node (ref "U22") (pin "4") (pinfunction "A3_4") (pintype "input"))
      (node (ref "U23") (pin "4") (pinfunction "A3_4") (pintype "input"))
      (node (ref "U24") (pin "4") (pinfunction "A3_4") (pintype "input"))
      (node (ref "U25") (pin "4") (pinfunction "A3_4") (pintype "input"))
      (node (ref "U26") (pin "4") (pinfunction "A3_4") (pintype "input"))
    )
    (net (code "120") (name "ROM_ADDR4") (class "Default")
      (node (ref "U20") (pin "3") (pinfunction "A4_3") (pintype "input"))
      (node (ref "U21") (pin "3") (pinfunction "A4_3") (pintype "input"))
      (node (ref "U22") (pin "3") (pinfunction "A4_3") (pintype "input"))
      (node (ref "U23") (pin "3") (pinfunction "A4_3") (pintype "input"))
      (node (ref "U24") (pin "3") (pinfunction "A4_3") (pintype "input"))
      (node (ref "U25") (pin "3") (pinfunction "A4_3") (pintype "input"))
      (node (ref "U26") (pin "3") (pinfunction "A4_3") (pintype "input"))
    )
    (net (code "121") (name "ROM_ADDR5") (class "Default")
      (node (ref "U20") (pin "2") (pinfunction "A5_2") (pintype "input"))
      (node (ref "U21") (pin "2") (pinfunction "A5_2") (pintype "input"))
      (node (ref "U22") (pin "2") (pinfunction "A5_2") (pintype "input"))
      (node (ref "U23") (pin "2") (pinfunction "A5_2") (pintype "input"))
      (node (ref "U24") (pin "2") (pinfunction "A5_2") (pintype "input"))
      (node (ref "U25") (pin "2") (pinfunction "A5_2") (pintype "input"))
      (node (ref "U26") (pin "2") (pinfunction "A5_2") (pintype "input"))
    )
    (net (code "122") (name "ROM_ADDR6") (class "Default")
      (node (ref "U20") (pin "1") (pinfunction "A6_1") (pintype "input"))
      (node (ref "U21") (pin "1") (pinfunction "A6_1") (pintype "input"))
      (node (ref "U22") (pin "1") (pinfunction "A6_1") (pintype "input"))
      (node (ref "U23") (pin "1") (pinfunction "A6_1") (pintype "input"))
      (node (ref "U24") (pin "1") (pinfunction "A6_1") (pintype "input"))
      (node (ref "U25") (pin "1") (pinfunction "A6_1") (pintype "input"))
      (node (ref "U26") (pin "1") (pinfunction "A6_1") (pintype "input"))
    )
    (net (code "123") (name "ROM_ADDR7") (class "Default")
      (node (ref "U20") (pin "17") (pinfunction "A7_17") (pintype "input"))
      (node (ref "U21") (pin "17") (pinfunction "A7_17") (pintype "input"))
      (node (ref "U22") (pin "17") (pinfunction "A7_17") (pintype "input"))
      (node (ref "U23") (pin "17") (pinfunction "A7_17") (pintype "input"))
      (node (ref "U24") (pin "17") (pinfunction "A7_17") (pintype "input"))
      (node (ref "U25") (pin "17") (pinfunction "A7_17") (pintype "input"))
      (node (ref "U26") (pin "17") (pinfunction "A7_17") (pintype "input"))
    )
    (net (code "124") (name "ROM_ADDR8") (class "Default")
      (node (ref "U20") (pin "16") (pinfunction "A8_16") (pintype "input"))
      (node (ref "U21") (pin "16") (pinfunction "A8_16") (pintype "input"))
      (node (ref "U22") (pin "16") (pinfunction "A8_16") (pintype "input"))
      (node (ref "U23") (pin "16") (pinfunction "A8_16") (pintype "input"))
      (node (ref "U24") (pin "16") (pinfunction "A8_16") (pintype "input"))
      (node (ref "U25") (pin "16") (pinfunction "A8_16") (pintype "input"))
      (node (ref "U26") (pin "16") (pinfunction "A8_16") (pintype "input"))
    )
    (net (code "125") (name "ROM_ADDR9") (class "Default")
      (node (ref "U20") (pin "15") (pinfunction "A9_15") (pintype "input"))
      (node (ref "U21") (pin "15") (pinfunction "A9_15") (pintype "input"))
      (node (ref "U22") (pin "15") (pinfunction "A9_15") (pintype "input"))
      (node (ref "U23") (pin "15") (pinfunction "A9_15") (pintype "input"))
      (node (ref "U24") (pin "15") (pinfunction "A9_15") (pintype "input"))
      (node (ref "U25") (pin "15") (pinfunction "A9_15") (pintype "input"))
      (node (ref "U26") (pin "15") (pinfunction "A9_15") (pintype "input"))
    )
    (net (code "126") (name "ROM_~{CE}") (class "Default")
      (node (ref "U20") (pin "10") (pinfunction "~{CE2}_10") (pintype "input"))
      (node (ref "U21") (pin "10") (pinfunction "~{CE2}_10") (pintype "input"))
      (node (ref "U22") (pin "10") (pinfunction "~{CE2}_10") (pintype "input"))
      (node (ref "U23") (pin "10") (pinfunction "~{CE2}_10") (pintype "input"))
      (node (ref "U24") (pin "10") (pinfunction "~{CE2}_10") (pintype "input"))
      (node (ref "U25") (pin "10") (pinfunction "~{CE2}_10") (pintype "input"))
      (node (ref "U26") (pin "10") (pinfunction "~{CE2}_10") (pintype "input"))
    )
    (net (code "127") (name "SEQ_U67_D0") (class "Default")
      (node (ref "U60") (pin "11") (pinfunction "A1_11") (pintype "input"))
      (node (ref "U67") (pin "13") (pinfunction "D0_13") (pintype "input"))
    )
    (net (code "128") (name "SEQ_U67_D1") (class "Default")
      (node (ref "U60") (pin "13") (pinfunction "A2_13") (pintype "input"))
      (node (ref "U67") (pin "11") (pinfunction "D1_11") (pintype "input"))
    )
    (net (code "129") (name "SEQ_U67_D2") (class "Default")
      (node (ref "U60") (pin "15") (pinfunction "A3_15") (pintype "input"))
      (node (ref "U67") (pin "9") (pinfunction "D2_9") (pintype "input"))
    )
    (net (code "130") (name "SEQ_U67_D3") (class "Default")
      (node (ref "U60") (pin "17") (pinfunction "A4_17") (pintype "input"))
      (node (ref "U67") (pin "7") (pinfunction "D3_7") (pintype "input"))
    )
    (net (code "131") (name "SEQ_U67_~{RE}") (class "Default")
      (node (ref "U53") (pin "11") (pinfunction "Y4_11") (pintype "output"))
      (node (ref "U67") (pin "1") (pinfunction "~{RE}_1") (pintype "input"))
    )
    (net (code "132") (name "SEQ_U68_D0") (class "Default")
      (node (ref "U34") (pin "2") (pinfunction "1A_2") (pintype "input"))
      (node (ref "U60") (pin "2") (pinfunction "A1_2") (pintype "input"))
      (node (ref "U68") (pin "13") (pinfunction "D0_13") (pintype "input"))
    )
    (net (code "133") (name "SEQ_U68_D1") (class "Default")
      (node (ref "U34") (pin "5") (pinfunction "2A_5") (pintype "input"))
      (node (ref "U60") (pin "4") (pinfunction "A2_4") (pintype "input"))
      (node (ref "U68") (pin "11") (pinfunction "D1_11") (pintype "input"))
    )
    (net (code "134") (name "SEQ_U68_D2") (class "Default")
      (node (ref "U34") (pin "11") (pinfunction "3A_11") (pintype "input"))
      (node (ref "U60") (pin "6") (pinfunction "A3_6") (pintype "input"))
      (node (ref "U68") (pin "9") (pinfunction "D2_9") (pintype "input"))
    )
    (net (code "135") (name "SEQ_U68_D3") (class "Default")
      (node (ref "U34") (pin "14") (pinfunction "4A_14") (pintype "input"))
      (node (ref "U60") (pin "8") (pinfunction "A4_8") (pintype "input"))
      (node (ref "U68") (pin "7") (pinfunction "D3_7") (pintype "input"))
    )
    (net (code "136") (name "U5-10_U49-14") (class "Default")
      (node (ref "U49") (pin "14") (pinfunction "J_14") (pintype "input"))
      (node (ref "U5") (pin "10") (pinfunction "O_10") (pintype "output"))
    )
    (net (code "137") (name "U31-1_U43-1") (class "Default")
      (node (ref "U31") (pin "1") (pinfunction "~{A}/B_1") (pintype "input"))
      (node (ref "U43") (pin "1") (pinfunction "G_1") (pintype "input"))
    )
    (net (code "138") (name "U31-12_U56-4") (class "Default")
      (node (ref "U31") (pin "12") (pinfunction "4Y_12") (pintype "tri_state"))
      (node (ref "U56") (pin "4") (pinfunction "I_4") (pintype "input"))
    )
    (net (code "139") (name "U31-13_U5-8") (class "Default")
      (node (ref "U31") (pin "13") (pinfunction "4B_13") (pintype "input"))
      (node (ref "U5") (pin "8") (pinfunction "O_8") (pintype "output"))
    )
    (net (code "140") (name "U39-1_U40-1") (class "Default")
      (node (ref "U39") (pin "1") (pinfunction "OC_1") (pintype "input"))
      (node (ref "U40") (pin "1") (pinfunction "OC_1") (pintype "input"))
    )
    (net (code "141") (name "U40-2_U32-3") (class "Default")
      (node (ref "U32") (pin "3") (pinfunction "1B_3") (pintype "input"))
      (node (ref "U40") (pin "2") (pinfunction "1Q_2") (pintype "tri_state"))
    )
    (net (code "142") (name "U40-19_U43-19") (class "Default")
      (node (ref "U40") (pin "19") (pinfunction "8Q_19") (pintype "tri_state"))
      (node (ref "U43") (pin "19") (pinfunction "G_19") (pintype "input"))
    )
    (net (code "143") (name "U43-3_U46-3") (class "Default")
      (node (ref "U43") (pin "3") (pinfunction "Y4_3") (pintype "tri_state"))
      (node (ref "U46") (pin "3") (pinfunction "Y4_3") (pintype "tri_state"))
    )
    (net (code "144") (name "U43-5_U46-5_U56-1") (class "Default")
      (node (ref "U43") (pin "5") (pinfunction "Y3_5") (pintype "tri_state"))
      (node (ref "U46") (pin "5") (pinfunction "Y3_5") (pintype "tri_state"))
      (node (ref "U56") (pin "1") (pinfunction "G_1") (pintype "input"))
    )
    (net (code "145") (name "U43-7_U46-7") (class "Default")
      (node (ref "U43") (pin "7") (pinfunction "Y2_7") (pintype "tri_state"))
      (node (ref "U46") (pin "7") (pinfunction "Y2_7") (pintype "tri_state"))
    )
    (net (code "146") (name "U43-9_U46-9_U56-12") (class "Default")
      (node (ref "U43") (pin "9") (pinfunction "Y1_9") (pintype "tri_state"))
      (node (ref "U46") (pin "9") (pinfunction "Y1_9") (pintype "tri_state"))
      (node (ref "U56") (pin "12") (pinfunction "E_12") (pintype "input"))
    )
    (net (code "147") (name "U43-12_U46-12_U56-11") (class "Default")
      (node (ref "U43") (pin "12") (pinfunction "Y4_12") (pintype "tri_state"))
      (node (ref "U46") (pin "12") (pinfunction "Y4_12") (pintype "tri_state"))
      (node (ref "U56") (pin "11") (pinfunction "D_11") (pintype "input"))
    )
    (net (code "148") (name "U43-14_U46-14") (class "Default")
      (node (ref "U43") (pin "14") (pinfunction "Y3_14") (pintype "tri_state"))
      (node (ref "U46") (pin "14") (pinfunction "Y3_14") (pintype "tri_state"))
    )
    (net (code "149") (name "U43-16_U46-16") (class "Default")
      (node (ref "U43") (pin "16") (pinfunction "Y2_16") (pintype "tri_state"))
      (node (ref "U46") (pin "16") (pinfunction "Y2_16") (pintype "tri_state"))
    )
    (net (code "150") (name "U43-18_U46-18_U56-8_U32-2") (class "Default")
      (node (ref "U32") (pin "2") (pinfunction "1A_2") (pintype "input"))
      (node (ref "U43") (pin "18") (pinfunction "Y1_18") (pintype "tri_state"))
      (node (ref "U46") (pin "18") (pinfunction "Y1_18") (pintype "tri_state"))
      (node (ref "U56") (pin "8") (pinfunction "A_8") (pintype "input"))
    )
    (net (code "151") (name "U45-13_U49-9") (class "Default")
      (node (ref "U45") (pin "13") (pinfunction "A2_13") (pintype "input"))
      (node (ref "U49") (pin "9") (pinfunction "~{Q}_9") (pintype "output"))
    )
    (net (code "152") (name "U45-15_U49-7") (class "Default")
      (node (ref "U45") (pin "15") (pinfunction "A3_15") (pintype "input"))
      (node (ref "U49") (pin "7") (pinfunction "~{Q}_7") (pintype "output"))
    )
    (net (code "153") (name "U45-17_U56-5") (class "Default")
      (node (ref "U45") (pin "17") (pinfunction "A4_17") (pintype "input"))
      (node (ref "U56") (pin "5") (pinfunction "SEV_5") (pintype "output"))
    )
    (net (code "154") (name "U53-10_U49-3") (class "Default")
      (node (ref "U49") (pin "3") (pinfunction "K_3") (pintype "input"))
      (node (ref "U53") (pin "10") (pinfunction "Y5_10") (pintype "output"))
    )
    (net (code "155") (name "U53-12_U40-11") (class "Default")
      (node (ref "U40") (pin "11") (pinfunction "CLK_11") (pintype "input"))
      (node (ref "U53") (pin "12") (pinfunction "Y3_12") (pintype "output"))
    )
    (net (code "156") (name "U53-13_U39-11") (class "Default")
      (node (ref "U39") (pin "11") (pinfunction "CLK_11") (pintype "input"))
      (node (ref "U53") (pin "13") (pinfunction "Y2_13") (pintype "output"))
    )
    (net (code "157") (name "U56-9_U32-5") (class "Default")
      (node (ref "U32") (pin "5") (pinfunction "2A_5") (pintype "input"))
      (node (ref "U56") (pin "9") (pinfunction "B_9") (pintype "input"))
    )
    (net (code "158") (name "U58-Q0_U59_Q3") (class "Default")
      (node (ref "U58") (pin "21") (pinfunction "Q0_21") (pintype "bidirectional"))
      (node (ref "U59") (pin "16") (pinfunction "Q3_16") (pintype "bidirectional"))
    )
    (net (code "159") (name "U58-RAM0_U59_RAM3") (class "Default")
      (node (ref "U58") (pin "9") (pinfunction "RAM0_9") (pintype "bidirectional"))
      (node (ref "U59") (pin "8") (pinfunction "RAM3_8") (pintype "bidirectional"))
    )
    (net (code "160") (name "U58_CN+4-U59_CN") (class "Default")
      (node (ref "U58") (pin "33") (pinfunction "CN+4_33") (pintype "output"))
      (node (ref "U59") (pin "29") (pinfunction "CN_29") (pintype "input"))
    )
    (net (code "161") (name "U60-19_U34-1") (class "Default")
      (node (ref "U34") (pin "1") (pinfunction "~{A}/B_1") (pintype "input"))
      (node (ref "U60") (pin "19") (pinfunction "G_19") (pintype "input"))
    )
    (net (code "162") (name "unconnected-(P1-Pad6A)") (class "Default")
      (node (ref "P1") (pin "6A") (pinfunction "6A_6A") (pintype "passive"))
    )
    (net (code "163") (name "unconnected-(P1-Pad6B)") (class "Default")
      (node (ref "P1") (pin "6B") (pinfunction "6B_6B") (pintype "passive"))
    )
    (net (code "164") (name "unconnected-(P1-Pad8A)") (class "Default")
      (node (ref "P1") (pin "8A") (pinfunction "8A_8A") (pintype "passive"))
    )
    (net (code "165") (name "unconnected-(P1-Pad8B)") (class "Default")
      (node (ref "P1") (pin "8B") (pinfunction "8B_8B") (pintype "passive"))
    )
    (net (code "166") (name "unconnected-(P1-Pad10A)") (class "Default")
      (node (ref "P1") (pin "10A") (pinfunction "10A_10A") (pintype "passive"))
    )
    (net (code "167") (name "unconnected-(P1-Pad10B)") (class "Default")
      (node (ref "P1") (pin "10B") (pinfunction "10B_10B") (pintype "passive"))
    )
    (net (code "168") (name "unconnected-(P1-Pad11B)") (class "Default")
      (node (ref "P1") (pin "11B") (pinfunction "11B_11B") (pintype "passive"))
    )
    (net (code "169") (name "unconnected-(P1B-1A-Pad21A)") (class "Default")
      (node (ref "P1") (pin "21A") (pinfunction "1A_21A") (pintype "passive"))
    )
    (net (code "170") (name "unconnected-(P1B-2A-Pad22A)") (class "Default")
      (node (ref "P1") (pin "22A") (pinfunction "2A_22A") (pintype "passive"))
    )
    (net (code "171") (name "unconnected-(P1B-3A-Pad23A)") (class "Default")
      (node (ref "P1") (pin "23A") (pinfunction "3A_23A") (pintype "passive"))
    )
    (net (code "172") (name "unconnected-(P1B-4B-Pad24B)") (class "Default")
      (node (ref "P1") (pin "24B") (pinfunction "4B_24B") (pintype "passive"))
    )
    (net (code "173") (name "unconnected-(P1B-5B-Pad25B)") (class "Default")
      (node (ref "P1") (pin "25B") (pinfunction "5B_25B") (pintype "passive"))
    )
    (net (code "174") (name "unconnected-(P1B-10A-Pad30A)") (class "Default")
      (node (ref "P1") (pin "30A") (pinfunction "10A_30A") (pintype "passive"))
    )
    (net (code "175") (name "unconnected-(P1B-10B-Pad30B)") (class "Default")
      (node (ref "P1") (pin "30B") (pinfunction "10B_30B") (pintype "passive"))
    )
    (net (code "176") (name "unconnected-(P1B-13A-Pad33A)") (class "Default")
      (node (ref "P1") (pin "33A") (pinfunction "13A_33A") (pintype "passive"))
    )
    (net (code "177") (name "unconnected-(P1B-13B-Pad33B)") (class "Default")
      (node (ref "P1") (pin "33B") (pinfunction "13B_33B") (pintype "passive"))
    )
    (net (code "178") (name "unconnected-(P1B-14A-Pad34A)") (class "Default")
      (node (ref "P1") (pin "34A") (pinfunction "14A_34A") (pintype "passive"))
    )
    (net (code "179") (name "unconnected-(P1B-14B-Pad34B)") (class "Default")
      (node (ref "P1") (pin "34B") (pinfunction "14B_34B") (pintype "passive"))
    )
    (net (code "180") (name "unconnected-(P1B-15A-Pad35A)") (class "Default")
      (node (ref "P1") (pin "35A") (pinfunction "15A_35A") (pintype "passive"))
    )
    (net (code "181") (name "unconnected-(P1B-15B-Pad35B)") (class "Default")
      (node (ref "P1") (pin "35B") (pinfunction "15B_35B") (pintype "passive"))
    )
    (net (code "182") (name "unconnected-(P1B-16A-Pad36A)") (class "Default")
      (node (ref "P1") (pin "36A") (pinfunction "16A_36A") (pintype "passive"))
    )
    (net (code "183") (name "unconnected-(P1B-16B-Pad36B)") (class "Default")
      (node (ref "P1") (pin "36B") (pinfunction "16B_36B") (pintype "passive"))
    )
    (net (code "184") (name "unconnected-(P1B-17A-Pad37A)") (class "Default")
      (node (ref "P1") (pin "37A") (pinfunction "17A_37A") (pintype "passive"))
    )
    (net (code "185") (name "unconnected-(P1B-17B-Pad37B)") (class "Default")
      (node (ref "P1") (pin "37B") (pinfunction "17B_37B") (pintype "passive"))
    )
    (net (code "186") (name "unconnected-(P1B-18A-Pad38A)") (class "Default")
      (node (ref "P1") (pin "38A") (pinfunction "18A_38A") (pintype "passive"))
    )
    (net (code "187") (name "unconnected-(P1B-18B-Pad38B)") (class "Default")
      (node (ref "P1") (pin "38B") (pinfunction "18B_38B") (pintype "passive"))
    )
    (net (code "188") (name "unconnected-(P1B-19A-Pad39A)") (class "Default")
      (node (ref "P1") (pin "39A") (pinfunction "19A_39A") (pintype "passive"))
    )
    (net (code "189") (name "unconnected-(P1B-19B-Pad39B)") (class "Default")
      (node (ref "P1") (pin "39B") (pinfunction "19B_39B") (pintype "passive"))
    )
    (net (code "190") (name "unconnected-(P1B-20A-Pad40A)") (class "Default")
      (node (ref "P1") (pin "40A") (pinfunction "20A_40A") (pintype "passive"))
    )
    (net (code "191") (name "unconnected-(P1B-20B-Pad40B)") (class "Default")
      (node (ref "P1") (pin "40B") (pinfunction "20B_40B") (pintype "passive"))
    )
    (net (code "192") (name "unconnected-(P1C-8A-Pad48A)") (class "Default")
      (node (ref "P1") (pin "48A") (pinfunction "8A_48A") (pintype "passive"))
    )
    (net (code "193") (name "unconnected-(P1C-8B-Pad48B)") (class "Default")
      (node (ref "P1") (pin "48B") (pinfunction "8B_48B") (pintype "passive"))
    )
    (net (code "194") (name "unconnected-(P1C-9A-Pad49A)") (class "Default")
      (node (ref "P1") (pin "49A") (pinfunction "9A_49A") (pintype "passive"))
    )
    (net (code "195") (name "unconnected-(P1C-9B-Pad49B)") (class "Default")
      (node (ref "P1") (pin "49B") (pinfunction "9B_49B") (pintype "passive"))
    )
    (net (code "196") (name "unconnected-(P1C-10A-Pad50A)") (class "Default")
      (node (ref "P1") (pin "50A") (pinfunction "10A_50A") (pintype "passive"))
    )
    (net (code "197") (name "unconnected-(P1C-10B-Pad50B)") (class "Default")
      (node (ref "P1") (pin "50B") (pinfunction "10B_50B") (pintype "passive"))
    )
    (net (code "198") (name "unconnected-(P1C-12B-Pad52B)") (class "Default")
      (node (ref "P1") (pin "52B") (pinfunction "12B_52B") (pintype "passive"))
    )
    (net (code "199") (name "unconnected-(P1C-13A-Pad53A)") (class "Default")
      (node (ref "P1") (pin "53A") (pinfunction "13A_53A") (pintype "passive"))
    )
    (net (code "200") (name "unconnected-(P1C-13B-Pad53B)") (class "Default")
      (node (ref "P1") (pin "53B") (pinfunction "13B_53B") (pintype "passive"))
    )
    (net (code "201") (name "unconnected-(P1C-18B-Pad58B)") (class "Default")
      (node (ref "P1") (pin "58B") (pinfunction "18B_58B") (pintype "passive"))
    )
    (net (code "202") (name "unconnected-(P1C-19A-Pad59A)") (class "Default")
      (node (ref "P1") (pin "59A") (pinfunction "19A_59A") (pintype "passive"))
    )
    (net (code "203") (name "unconnected-(P1C-19B-Pad59B)") (class "Default")
      (node (ref "P1") (pin "59B") (pinfunction "19B_59B") (pintype "passive"))
    )
    (net (code "204") (name "unconnected-(P1C-20A-Pad60A)") (class "Default")
      (node (ref "P1") (pin "60A") (pinfunction "20A_60A") (pintype "passive"))
    )
    (net (code "205") (name "unconnected-(P1C-20B-Pad60B)") (class "Default")
      (node (ref "P1") (pin "60B") (pinfunction "20B_60B") (pintype "passive"))
    )
    (net (code "206") (name "unconnected-(P1D-5A-Pad65A)") (class "Default")
      (node (ref "P1") (pin "65A") (pinfunction "5A_65A") (pintype "passive"))
    )
    (net (code "207") (name "unconnected-(P1D-10A-Pad70A)") (class "Default")
      (node (ref "P1") (pin "70A") (pinfunction "10A_70A") (pintype "passive"))
    )
    (net (code "208") (name "unconnected-(P1D-10B-Pad70B)") (class "Default")
      (node (ref "P1") (pin "70B") (pinfunction "10B_70B") (pintype "passive"))
    )
    (net (code "209") (name "unconnected-(P1D-11B-Pad71B)") (class "Default")
      (node (ref "P1") (pin "71B") (pinfunction "11B_71B") (pintype "passive"))
    )
    (net (code "210") (name "unconnected-(P1D-12B-Pad72B)") (class "Default")
      (node (ref "P1") (pin "72B") (pinfunction "12B_72B") (pintype "passive"))
    )
    (net (code "211") (name "unconnected-(P1D-13A-Pad73A)") (class "Default")
      (node (ref "P1") (pin "73A") (pinfunction "13A_73A") (pintype "passive"))
    )
    (net (code "212") (name "unconnected-(P1D-13B-Pad73B)") (class "Default")
      (node (ref "P1") (pin "73B") (pinfunction "13B_73B") (pintype "passive"))
    )
    (net (code "213") (name "unconnected-(P1D-14A-Pad74A)") (class "Default")
      (node (ref "P1") (pin "74A") (pinfunction "14A_74A") (pintype "passive"))
    )
    (net (code "214") (name "unconnected-(P1D-14B-Pad74B)") (class "Default")
      (node (ref "P1") (pin "74B") (pinfunction "14B_74B") (pintype "passive"))
    )
    (net (code "215") (name "unconnected-(P1D-15B-Pad75B)") (class "Default")
      (node (ref "P1") (pin "75B") (pinfunction "15B_75B") (pintype "passive"))
    )
    (net (code "216") (name "unconnected-(P1D-16B-Pad76B)") (class "Default")
      (node (ref "P1") (pin "76B") (pinfunction "16B_76B") (pintype "passive"))
    )
    (net (code "217") (name "unconnected-(P1D-17A-Pad77A)") (class "Default")
      (node (ref "P1") (pin "77A") (pinfunction "17A_77A") (pintype "passive"))
    )
    (net (code "218") (name "unconnected-(P1D-17B-Pad77B)") (class "Default")
      (node (ref "P1") (pin "77B") (pinfunction "17B_77B") (pintype "passive"))
    )
    (net (code "219") (name "unconnected-(P1D-18A-Pad78A)") (class "Default")
      (node (ref "P1") (pin "78A") (pinfunction "18A_78A") (pintype "passive"))
    )
    (net (code "220") (name "unconnected-(P1D-18B-Pad78B)") (class "Default")
      (node (ref "P1") (pin "78B") (pinfunction "18B_78B") (pintype "passive"))
    )
    (net (code "221") (name "unconnected-(P1D-19A-Pad79A)") (class "Default")
      (node (ref "P1") (pin "79A") (pinfunction "19A_79A") (pintype "passive"))
    )
    (net (code "222") (name "unconnected-(P1D-19B-Pad79B)") (class "Default")
      (node (ref "P1") (pin "79B") (pinfunction "19B_79B") (pintype "passive"))
    )
    (net (code "223") (name "unconnected-(P1D-20B-Pad80B)") (class "Default")
      (node (ref "P1") (pin "80B") (pinfunction "20B_80B") (pintype "passive"))
    )
    (net (code "224") (name "unconnected-(R21-Pad2)") (class "Default")
      (node (ref "R21") (pin "2") (pinfunction "2_2") (pintype "passive"))
    )
    (net (code "225") (name "unconnected-(RN1-B-Pad8)") (class "Default")
      (node (ref "RN1") (pin "8") (pinfunction "B_8") (pintype "passive"))
    )
    (net (code "226") (name "unconnected-(RN1-R1-Pad1)") (class "Default")
      (node (ref "RN1") (pin "1") (pinfunction "R1_1") (pintype "passive"))
    )
    (net (code "227") (name "unconnected-(RN1-R4-Pad4)") (class "Default")
      (node (ref "RN1") (pin "4") (pinfunction "R4_4") (pintype "passive"))
    )
    (net (code "228") (name "unconnected-(RN1-R5-Pad5)") (class "Default")
      (node (ref "RN1") (pin "5") (pinfunction "R5_5") (pintype "passive"))
    )
    (net (code "229") (name "unconnected-(RN1-R13-Pad14)") (class "Default")
      (node (ref "RN1") (pin "14") (pinfunction "R13_14") (pintype "passive"))
    )
    (net (code "230") (name "unconnected-(RN1-R14-Pad15)") (class "Default")
      (node (ref "RN1") (pin "15") (pinfunction "R14_15") (pintype "passive"))
    )
    (net (code "231") (name "unconnected-(U5D-O-Pad2)") (class "Default")
      (node (ref "U5") (pin "2") (pinfunction "O_2") (pintype "output"))
    )
    (net (code "232") (name "unconnected-(U5E-I-Pad3)") (class "Default")
      (node (ref "U5") (pin "3") (pinfunction "I_3") (pintype "input"))
    )
    (net (code "233") (name "unconnected-(U7A-CLK-Pad11)") (class "Default")
      (node (ref "U7") (pin "11") (pinfunction "CLK_11") (pintype "input"))
    )
    (net (code "234") (name "unconnected-(U7A-OC-Pad1)") (class "Default")
      (node (ref "U7") (pin "1") (pinfunction "OC_1") (pintype "input"))
    )
    (net (code "235") (name "unconnected-(U20A-D0-Pad14)") (class "Default")
      (node (ref "U20") (pin "14") (pinfunction "D0_14") (pintype "tri_state"))
    )
    (net (code "236") (name "unconnected-(U20A-D1-Pad13)") (class "Default")
      (node (ref "U20") (pin "13") (pinfunction "D1_13") (pintype "tri_state"))
    )
    (net (code "237") (name "unconnected-(U20A-D2-Pad12)") (class "Default")
      (node (ref "U20") (pin "12") (pinfunction "D2_12") (pintype "tri_state"))
    )
    (net (code "238") (name "unconnected-(U20A-D3-Pad11)") (class "Default")
      (node (ref "U20") (pin "11") (pinfunction "D3_11") (pintype "tri_state"))
    )
    (net (code "239") (name "unconnected-(U21A-D0-Pad14)") (class "Default")
      (node (ref "U21") (pin "14") (pinfunction "D0_14") (pintype "tri_state"))
    )
    (net (code "240") (name "unconnected-(U21A-D1-Pad13)") (class "Default")
      (node (ref "U21") (pin "13") (pinfunction "D1_13") (pintype "tri_state"))
    )
    (net (code "241") (name "unconnected-(U21A-D2-Pad12)") (class "Default")
      (node (ref "U21") (pin "12") (pinfunction "D2_12") (pintype "tri_state"))
    )
    (net (code "242") (name "unconnected-(U21A-D3-Pad11)") (class "Default")
      (node (ref "U21") (pin "11") (pinfunction "D3_11") (pintype "tri_state"))
    )
    (net (code "243") (name "unconnected-(U22A-D0-Pad14)") (class "Default")
      (node (ref "U22") (pin "14") (pinfunction "D0_14") (pintype "tri_state"))
    )
    (net (code "244") (name "unconnected-(U22A-D1-Pad13)") (class "Default")
      (node (ref "U22") (pin "13") (pinfunction "D1_13") (pintype "tri_state"))
    )
    (net (code "245") (name "unconnected-(U22A-D2-Pad12)") (class "Default")
      (node (ref "U22") (pin "12") (pinfunction "D2_12") (pintype "tri_state"))
    )
    (net (code "246") (name "unconnected-(U22A-D3-Pad11)") (class "Default")
      (node (ref "U22") (pin "11") (pinfunction "D3_11") (pintype "tri_state"))
    )
    (net (code "247") (name "unconnected-(U23A-D0-Pad14)") (class "Default")
      (node (ref "U23") (pin "14") (pinfunction "D0_14") (pintype "tri_state"))
    )
    (net (code "248") (name "unconnected-(U23A-D1-Pad13)") (class "Default")
      (node (ref "U23") (pin "13") (pinfunction "D1_13") (pintype "tri_state"))
    )
    (net (code "249") (name "unconnected-(U23A-D2-Pad12)") (class "Default")
      (node (ref "U23") (pin "12") (pinfunction "D2_12") (pintype "tri_state"))
    )
    (net (code "250") (name "unconnected-(U23A-D3-Pad11)") (class "Default")
      (node (ref "U23") (pin "11") (pinfunction "D3_11") (pintype "tri_state"))
    )
    (net (code "251") (name "unconnected-(U24A-D0-Pad14)") (class "Default")
      (node (ref "U24") (pin "14") (pinfunction "D0_14") (pintype "tri_state"))
    )
    (net (code "252") (name "unconnected-(U24A-D1-Pad13)") (class "Default")
      (node (ref "U24") (pin "13") (pinfunction "D1_13") (pintype "tri_state"))
    )
    (net (code "253") (name "unconnected-(U24A-D2-Pad12)") (class "Default")
      (node (ref "U24") (pin "12") (pinfunction "D2_12") (pintype "tri_state"))
    )
    (net (code "254") (name "unconnected-(U24A-D3-Pad11)") (class "Default")
      (node (ref "U24") (pin "11") (pinfunction "D3_11") (pintype "tri_state"))
    )
    (net (code "255") (name "unconnected-(U25A-D0-Pad14)") (class "Default")
      (node (ref "U25") (pin "14") (pinfunction "D0_14") (pintype "tri_state"))
    )
    (net (code "256") (name "unconnected-(U25A-D1-Pad13)") (class "Default")
      (node (ref "U25") (pin "13") (pinfunction "D1_13") (pintype "tri_state"))
    )
    (net (code "257") (name "unconnected-(U25A-D2-Pad12)") (class "Default")
      (node (ref "U25") (pin "12") (pinfunction "D2_12") (pintype "tri_state"))
    )
    (net (code "258") (name "unconnected-(U25A-D3-Pad11)") (class "Default")
      (node (ref "U25") (pin "11") (pinfunction "D3_11") (pintype "tri_state"))
    )
    (net (code "259") (name "unconnected-(U26A-D0-Pad14)") (class "Default")
      (node (ref "U26") (pin "14") (pinfunction "D0_14") (pintype "tri_state"))
    )
    (net (code "260") (name "unconnected-(U26A-D1-Pad13)") (class "Default")
      (node (ref "U26") (pin "13") (pinfunction "D1_13") (pintype "tri_state"))
    )
    (net (code "261") (name "unconnected-(U26A-D2-Pad12)") (class "Default")
      (node (ref "U26") (pin "12") (pinfunction "D2_12") (pintype "tri_state"))
    )
    (net (code "262") (name "unconnected-(U26A-D3-Pad11)") (class "Default")
      (node (ref "U26") (pin "11") (pinfunction "D3_11") (pintype "tri_state"))
    )
    (net (code "263") (name "unconnected-(U30A-3B-Pad10)") (class "Default")
      (node (ref "U30") (pin "10") (pinfunction "3B_10") (pintype "input"))
    )
    (net (code "264") (name "unconnected-(U30A-4B-Pad13)") (class "Default")
      (node (ref "U30") (pin "13") (pinfunction "4B_13") (pintype "input"))
    )
    (net (code "265") (name "unconnected-(U30A-G-Pad15)") (class "Default")
      (node (ref "U30") (pin "15") (pinfunction "G_15") (pintype "input"))
    )
    (net (code "266") (name "unconnected-(U30A-~{A}{slash}B-Pad1)") (class "Default")
      (node (ref "U30") (pin "1") (pinfunction "~{A}/B_1") (pintype "input"))
    )
    (net (code "267") (name "unconnected-(U31A-1A-Pad2)") (class "Default")
      (node (ref "U31") (pin "2") (pinfunction "1A_2") (pintype "input"))
    )
    (net (code "268") (name "unconnected-(U31A-1B-Pad3)") (class "Default")
      (node (ref "U31") (pin "3") (pinfunction "1B_3") (pintype "input"))
    )
    (net (code "269") (name "unconnected-(U31A-1Y-Pad4)") (class "Default")
      (node (ref "U31") (pin "4") (pinfunction "1Y_4") (pintype "tri_state"))
    )
    (net (code "270") (name "unconnected-(U31A-2A-Pad5)") (class "Default")
      (node (ref "U31") (pin "5") (pinfunction "2A_5") (pintype "input"))
    )
    (net (code "271") (name "unconnected-(U31A-2B-Pad6)") (class "Default")
      (node (ref "U31") (pin "6") (pinfunction "2B_6") (pintype "input"))
    )
    (net (code "272") (name "unconnected-(U31A-2Y-Pad7)") (class "Default")
      (node (ref "U31") (pin "7") (pinfunction "2Y_7") (pintype "tri_state"))
    )
    (net (code "273") (name "unconnected-(U31A-3A-Pad11)") (class "Default")
      (node (ref "U31") (pin "11") (pinfunction "3A_11") (pintype "input"))
    )
    (net (code "274") (name "unconnected-(U31A-3B-Pad10)") (class "Default")
      (node (ref "U31") (pin "10") (pinfunction "3B_10") (pintype "input"))
    )
    (net (code "275") (name "unconnected-(U31A-3Y-Pad9)") (class "Default")
      (node (ref "U31") (pin "9") (pinfunction "3Y_9") (pintype "tri_state"))
    )
    (net (code "276") (name "unconnected-(U31A-G-Pad15)") (class "Default")
      (node (ref "U31") (pin "15") (pinfunction "G_15") (pintype "input"))
    )
    (net (code "277") (name "unconnected-(U32A-3A-Pad11)") (class "Default")
      (node (ref "U32") (pin "11") (pinfunction "3A_11") (pintype "input"))
    )
    (net (code "278") (name "unconnected-(U32A-4A-Pad14)") (class "Default")
      (node (ref "U32") (pin "14") (pinfunction "4A_14") (pintype "input"))
    )
    (net (code "279") (name "unconnected-(U32A-G-Pad15)") (class "Default")
      (node (ref "U32") (pin "15") (pinfunction "G_15") (pintype "input"))
    )
    (net (code "280") (name "unconnected-(U32A-~{A}{slash}B-Pad1)") (class "Default")
      (node (ref "U32") (pin "1") (pinfunction "~{A}/B_1") (pintype "input"))
    )
    (net (code "281") (name "unconnected-(U40A-6D-Pad14)") (class "Default")
      (node (ref "U40") (pin "14") (pinfunction "6D_14") (pintype "input"))
    )
    (net (code "282") (name "unconnected-(U44A-G-Pad1)") (class "Default")
      (node (ref "U44") (pin "1") (pinfunction "G_1") (pintype "input"))
    )
    (net (code "283") (name "unconnected-(U44B-G-Pad19)") (class "Default")
      (node (ref "U44") (pin "19") (pinfunction "G_19") (pintype "input"))
    )
    (net (code "284") (name "unconnected-(U45A-G-Pad1)") (class "Default")
      (node (ref "U45") (pin "1") (pinfunction "G_1") (pintype "input"))
    )
    (net (code "285") (name "unconnected-(U45B-G-Pad19)") (class "Default")
      (node (ref "U45") (pin "19") (pinfunction "G_19") (pintype "input"))
    )
    (net (code "286") (name "unconnected-(U46A-G-Pad1)") (class "Default")
      (node (ref "U46") (pin "1") (pinfunction "G_1") (pintype "input"))
    )
    (net (code "287") (name "unconnected-(U46B-G-Pad19)") (class "Default")
      (node (ref "U46") (pin "19") (pinfunction "G_19") (pintype "input"))
    )
    (net (code "288") (name "unconnected-(U49A-PRE-Pad5)") (class "Default")
      (node (ref "U49") (pin "5") (pinfunction "PRE_5") (pintype "input"))
    )
    (net (code "289") (name "unconnected-(U49A-Q-Pad6)") (class "Default")
      (node (ref "U49") (pin "6") (pinfunction "Q_6") (pintype "output"))
    )
    (net (code "290") (name "unconnected-(U49B-CLK-Pad12)") (class "Default")
      (node (ref "U49") (pin "12") (pinfunction "CLK_12") (pintype "input"))
    )
    (net (code "291") (name "unconnected-(U49B-CLR-Pad15)") (class "Default")
      (node (ref "U49") (pin "15") (pinfunction "CLR_15") (pintype "input"))
    )
    (net (code "292") (name "unconnected-(U49B-K-Pad13)") (class "Default")
      (node (ref "U49") (pin "13") (pinfunction "K_13") (pintype "input"))
    )
    (net (code "293") (name "unconnected-(U49B-PRE-Pad11)") (class "Default")
      (node (ref "U49") (pin "11") (pinfunction "PRE_11") (pintype "input"))
    )
    (net (code "294") (name "unconnected-(U49B-Q-Pad10)") (class "Default")
      (node (ref "U49") (pin "10") (pinfunction "Q_10") (pintype "output"))
    )
    (net (code "295") (name "unconnected-(U53A-G1-Pad6)") (class "Default")
      (node (ref "U53") (pin "6") (pinfunction "G1_6") (pintype "input"))
    )
    (net (code "296") (name "unconnected-(U53A-Y0-Pad15)") (class "Default")
      (node (ref "U53") (pin "15") (pinfunction "Y0_15") (pintype "output"))
    )
    (net (code "297") (name "unconnected-(U53A-Y1-Pad14)") (class "Default")
      (node (ref "U53") (pin "14") (pinfunction "Y1_14") (pintype "output"))
    )
    (net (code "298") (name "unconnected-(U53A-Y6-Pad9)") (class "Default")
      (node (ref "U53") (pin "9") (pinfunction "Y6_9") (pintype "output"))
    )
    (net (code "299") (name "unconnected-(U53A-Y7-Pad7)") (class "Default")
      (node (ref "U53") (pin "7") (pinfunction "Y7_7") (pintype "output"))
    )
    (net (code "300") (name "unconnected-(U56A-C-Pad10)") (class "Default")
      (node (ref "U56") (pin "10") (pinfunction "C_10") (pintype "input"))
    )
    (net (code "301") (name "unconnected-(U56A-F-Pad13)") (class "Default")
      (node (ref "U56") (pin "13") (pinfunction "F_13") (pintype "input"))
    )
    (net (code "302") (name "unconnected-(U56A-H-Pad2)") (class "Default")
      (node (ref "U56") (pin "2") (pinfunction "H_2") (pintype "input"))
    )
    (net (code "303") (name "unconnected-(U56A-SOD-Pad6)") (class "Default")
      (node (ref "U56") (pin "6") (pinfunction "SOD_6") (pintype "output"))
    )
    (net (code "304") (name "unconnected-(U57A-I-Pad4)") (class "Default")
      (node (ref "U57") (pin "4") (pinfunction "I_4") (pintype "input"))
    )
    (net (code "305") (name "unconnected-(U57A-SOD-Pad6)") (class "Default")
      (node (ref "U57") (pin "6") (pinfunction "SOD_6") (pintype "output"))
    )
    (net (code "306") (name "unconnected-(U58A-CN-Pad29)") (class "Default")
      (node (ref "U58") (pin "29") (pinfunction "CN_29") (pintype "input"))
    )
    (net (code "307") (name "unconnected-(U58A-F3-Pad31)") (class "Default")
      (node (ref "U58") (pin "31") (pinfunction "F3_31") (pintype "output"))
    )
    (net (code "308") (name "unconnected-(U58A-OVR-Pad34)") (class "Default")
      (node (ref "U58") (pin "34") (pinfunction "OVR_34") (pintype "output"))
    )
    (net (code "309") (name "unconnected-(U58A-Q3-Pad16)") (class "Default")
      (node (ref "U58") (pin "16") (pinfunction "Q3_16") (pintype "bidirectional"))
    )
    (net (code "310") (name "unconnected-(U58A-RAM3-Pad8)") (class "Default")
      (node (ref "U58") (pin "8") (pinfunction "RAM3_8") (pintype "bidirectional"))
    )
    (net (code "311") (name "unconnected-(U58A-~{G}-Pad32)") (class "Default")
      (node (ref "U58") (pin "32") (pinfunction "~{G}_32") (pintype "output"))
    )
    (net (code "312") (name "unconnected-(U58A-~{P}-Pad35)") (class "Default")
      (node (ref "U58") (pin "35") (pinfunction "~{P}_35") (pintype "output"))
    )
    (net (code "313") (name "unconnected-(U59A-CN+4-Pad33)") (class "Default")
      (node (ref "U59") (pin "33") (pinfunction "CN+4_33") (pintype "output"))
    )
    (net (code "314") (name "unconnected-(U59A-F3-Pad31)") (class "Default")
      (node (ref "U59") (pin "31") (pinfunction "F3_31") (pintype "output"))
    )
    (net (code "315") (name "unconnected-(U59A-OVR-Pad34)") (class "Default")
      (node (ref "U59") (pin "34") (pinfunction "OVR_34") (pintype "output"))
    )
    (net (code "316") (name "unconnected-(U59A-Q0-Pad21)") (class "Default")
      (node (ref "U59") (pin "21") (pinfunction "Q0_21") (pintype "bidirectional"))
    )
    (net (code "317") (name "unconnected-(U59A-RAM0-Pad9)") (class "Default")
      (node (ref "U59") (pin "9") (pinfunction "RAM0_9") (pintype "bidirectional"))
    )
    (net (code "318") (name "unconnected-(U59A-~{G}-Pad32)") (class "Default")
      (node (ref "U59") (pin "32") (pinfunction "~{G}_32") (pintype "output"))
    )
    (net (code "319") (name "unconnected-(U59A-~{P}-Pad35)") (class "Default")
      (node (ref "U59") (pin "35") (pinfunction "~{P}_35") (pintype "output"))
    )
    (net (code "320") (name "unconnected-(U60A-G-Pad1)") (class "Default")
      (node (ref "U60") (pin "1") (pinfunction "G_1") (pintype "input"))
    )
    (net (code "321") (name "unconnected-(U60B-Y1-Pad9)") (class "Default")
      (node (ref "U60") (pin "9") (pinfunction "Y1_9") (pintype "tri_state"))
    )
    (net (code "322") (name "unconnected-(U60B-Y2-Pad7)") (class "Default")
      (node (ref "U60") (pin "7") (pinfunction "Y2_7") (pintype "tri_state"))
    )
    (net (code "323") (name "unconnected-(U60B-Y3-Pad5)") (class "Default")
      (node (ref "U60") (pin "5") (pinfunction "Y3_5") (pintype "tri_state"))
    )
    (net (code "324") (name "unconnected-(U60B-Y4-Pad3)") (class "Default")
      (node (ref "U60") (pin "3") (pinfunction "Y4_3") (pintype "tri_state"))
    )
    (net (code "325") (name "unconnected-(U67A-CN+4-Pad24)") (class "Default")
      (node (ref "U67") (pin "24") (pinfunction "CN+4_24") (pintype "output"))
    )
    (net (code "326") (name "unconnected-(U67A-CN-Pad23)") (class "Default")
      (node (ref "U67") (pin "23") (pinfunction "CN_23") (pintype "input"))
    )
    (net (code "327") (name "unconnected-(U67A-CP-Pad27)") (class "Default")
      (node (ref "U67") (pin "27") (pinfunction "CP_27") (pintype "input"))
    )
    (net (code "328") (name "unconnected-(U67A-PUP-Pad26)") (class "Default")
      (node (ref "U67") (pin "26") (pinfunction "PUP_26") (pintype "input"))
    )
    (net (code "329") (name "unconnected-(U67A-S0-Pad16)") (class "Default")
      (node (ref "U67") (pin "16") (pinfunction "S0_16") (pintype "input"))
    )
    (net (code "330") (name "unconnected-(U67A-S1-Pad17)") (class "Default")
      (node (ref "U67") (pin "17") (pinfunction "S1_17") (pintype "input"))
    )
    (net (code "331") (name "unconnected-(U67A-Y0-Pad18)") (class "Default")
      (node (ref "U67") (pin "18") (pinfunction "Y0_18") (pintype "output"))
    )
    (net (code "332") (name "unconnected-(U67A-Y1-Pad19)") (class "Default")
      (node (ref "U67") (pin "19") (pinfunction "Y1_19") (pintype "output"))
    )
    (net (code "333") (name "unconnected-(U67A-Y2-Pad20)") (class "Default")
      (node (ref "U67") (pin "20") (pinfunction "Y2_20") (pintype "output"))
    )
    (net (code "334") (name "unconnected-(U67A-Y3-Pad21)") (class "Default")
      (node (ref "U67") (pin "21") (pinfunction "Y3_21") (pintype "output"))
    )
    (net (code "335") (name "unconnected-(U67A-~{FE}-Pad25)") (class "Default")
      (node (ref "U67") (pin "25") (pinfunction "~{FE}_25") (pintype "input"))
    )
    (net (code "336") (name "unconnected-(U67A-~{OE}-Pad22)") (class "Default")
      (node (ref "U67") (pin "22") (pinfunction "~{OE}_22") (pintype "input"))
    )
    (net (code "337") (name "unconnected-(U67A-~{ZERO}-Pad15)") (class "Default")
      (node (ref "U67") (pin "15") (pinfunction "~{ZERO}_15") (pintype "input"))
    )
    (net (code "338") (name "unconnected-(U68A-CN+4-Pad24)") (class "Default")
      (node (ref "U68") (pin "24") (pinfunction "CN+4_24") (pintype "output"))
    )
    (net (code "339") (name "unconnected-(U68A-CN-Pad23)") (class "Default")
      (node (ref "U68") (pin "23") (pinfunction "CN_23") (pintype "input"))
    )
    (net (code "340") (name "unconnected-(U68A-CP-Pad27)") (class "Default")
      (node (ref "U68") (pin "27") (pinfunction "CP_27") (pintype "input"))
    )
    (net (code "341") (name "unconnected-(U68A-PUP-Pad26)") (class "Default")
      (node (ref "U68") (pin "26") (pinfunction "PUP_26") (pintype "input"))
    )
    (net (code "342") (name "unconnected-(U68A-S0-Pad16)") (class "Default")
      (node (ref "U68") (pin "16") (pinfunction "S0_16") (pintype "input"))
    )
    (net (code "343") (name "unconnected-(U68A-S1-Pad17)") (class "Default")
      (node (ref "U68") (pin "17") (pinfunction "S1_17") (pintype "input"))
    )
    (net (code "344") (name "unconnected-(U68A-Y0-Pad18)") (class "Default")
      (node (ref "U68") (pin "18") (pinfunction "Y0_18") (pintype "output"))
    )
    (net (code "345") (name "unconnected-(U68A-Y1-Pad19)") (class "Default")
      (node (ref "U68") (pin "19") (pinfunction "Y1_19") (pintype "output"))
    )
    (net (code "346") (name "unconnected-(U68A-Y2-Pad20)") (class "Default")
      (node (ref "U68") (pin "20") (pinfunction "Y2_20") (pintype "output"))
    )
    (net (code "347") (name "unconnected-(U68A-Y3-Pad21)") (class "Default")
      (node (ref "U68") (pin "21") (pinfunction "Y3_21") (pintype "output"))
    )
    (net (code "348") (name "unconnected-(U68A-~{FE}-Pad25)") (class "Default")
      (node (ref "U68") (pin "25") (pinfunction "~{FE}_25") (pintype "input"))
    )
    (net (code "349") (name "unconnected-(U68A-~{OE}-Pad22)") (class "Default")
      (node (ref "U68") (pin "22") (pinfunction "~{OE}_22") (pintype "input"))
    )
    (net (code "350") (name "unconnected-(U68A-~{RE}-Pad1)") (class "Default")
      (node (ref "U68") (pin "1") (pinfunction "~{RE}_1") (pintype "input"))
    )
    (net (code "351") (name "unconnected-(U68A-~{ZERO}-Pad15)") (class "Default")
      (node (ref "U68") (pin "15") (pinfunction "~{ZERO}_15") (pintype "input"))
    )
  )
)
